# signal_distribution_board.net
KiCad netlist of a schematic drawn in EAGLE
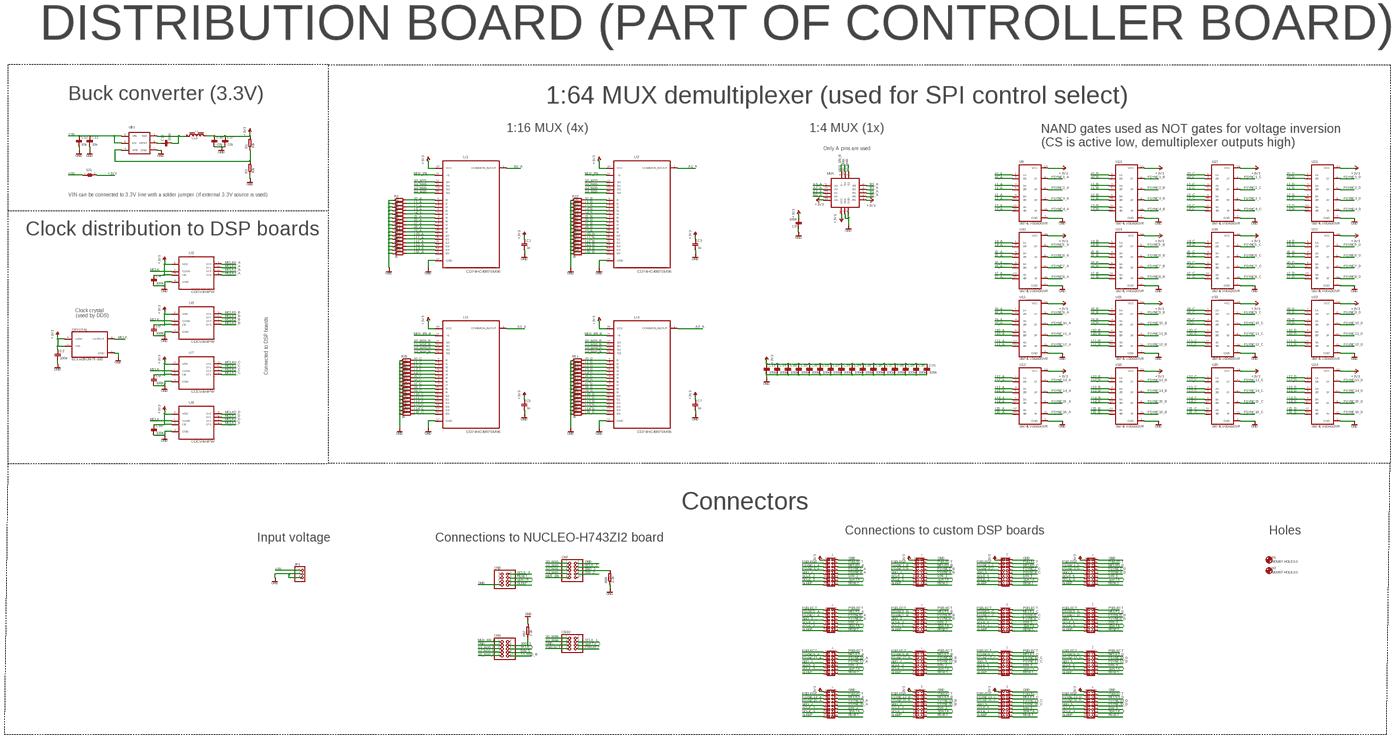
[diagram p0: schematic, sheet 1, overview]
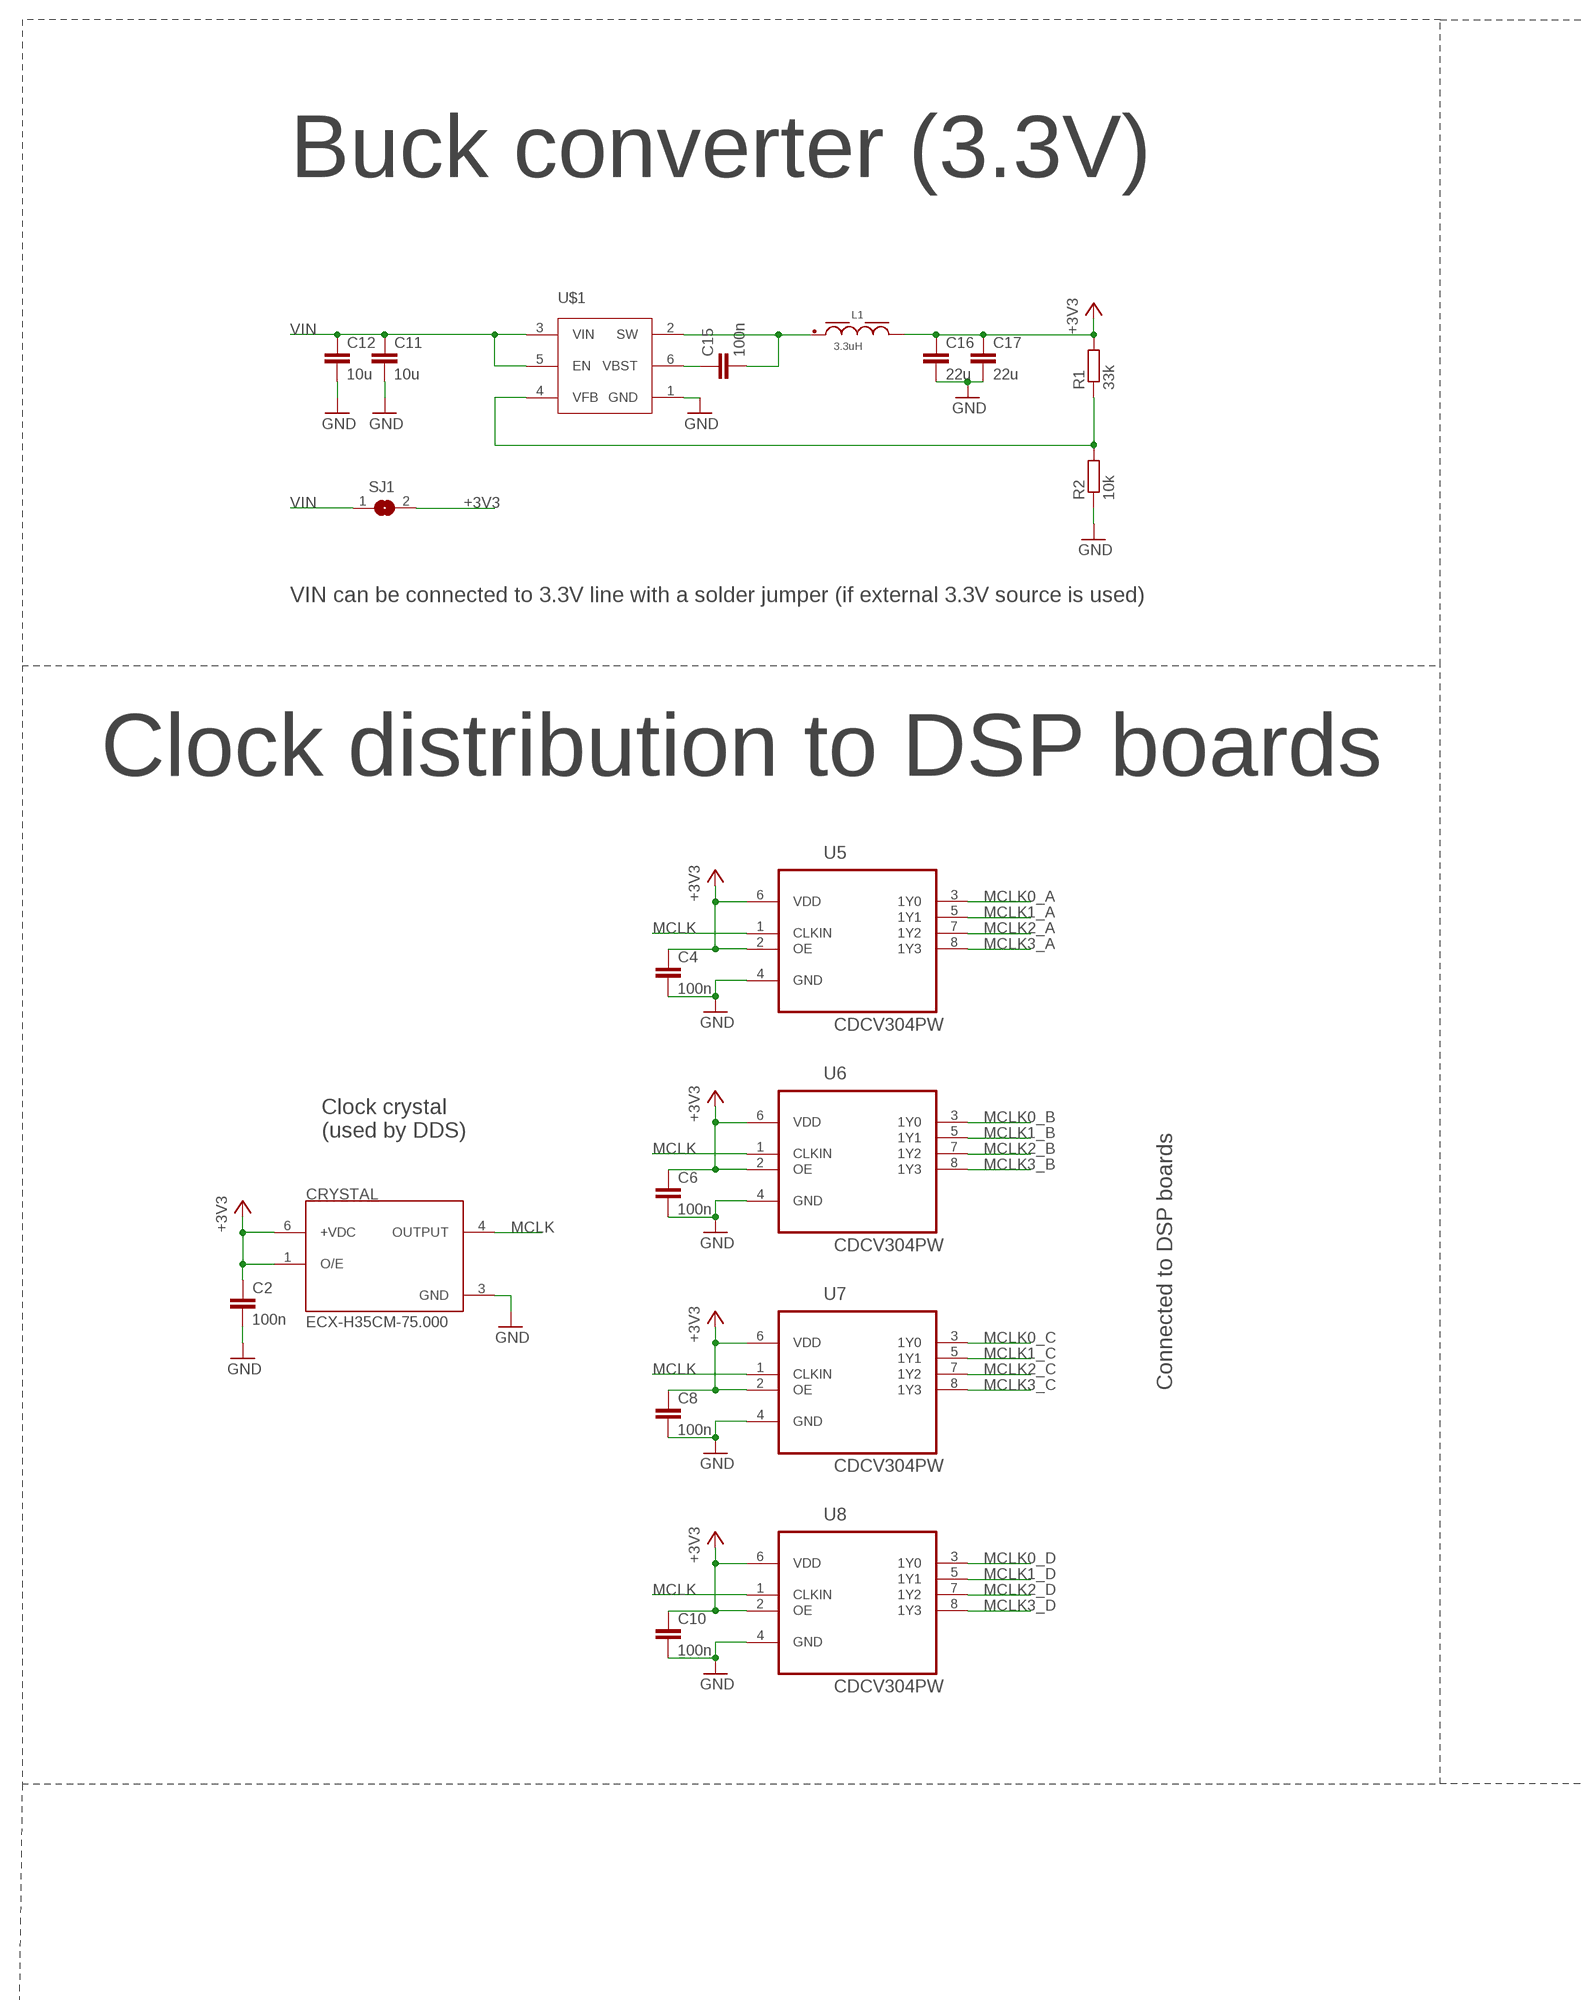
[diagram p1: schematic, sheet 1, part 1 of 8]
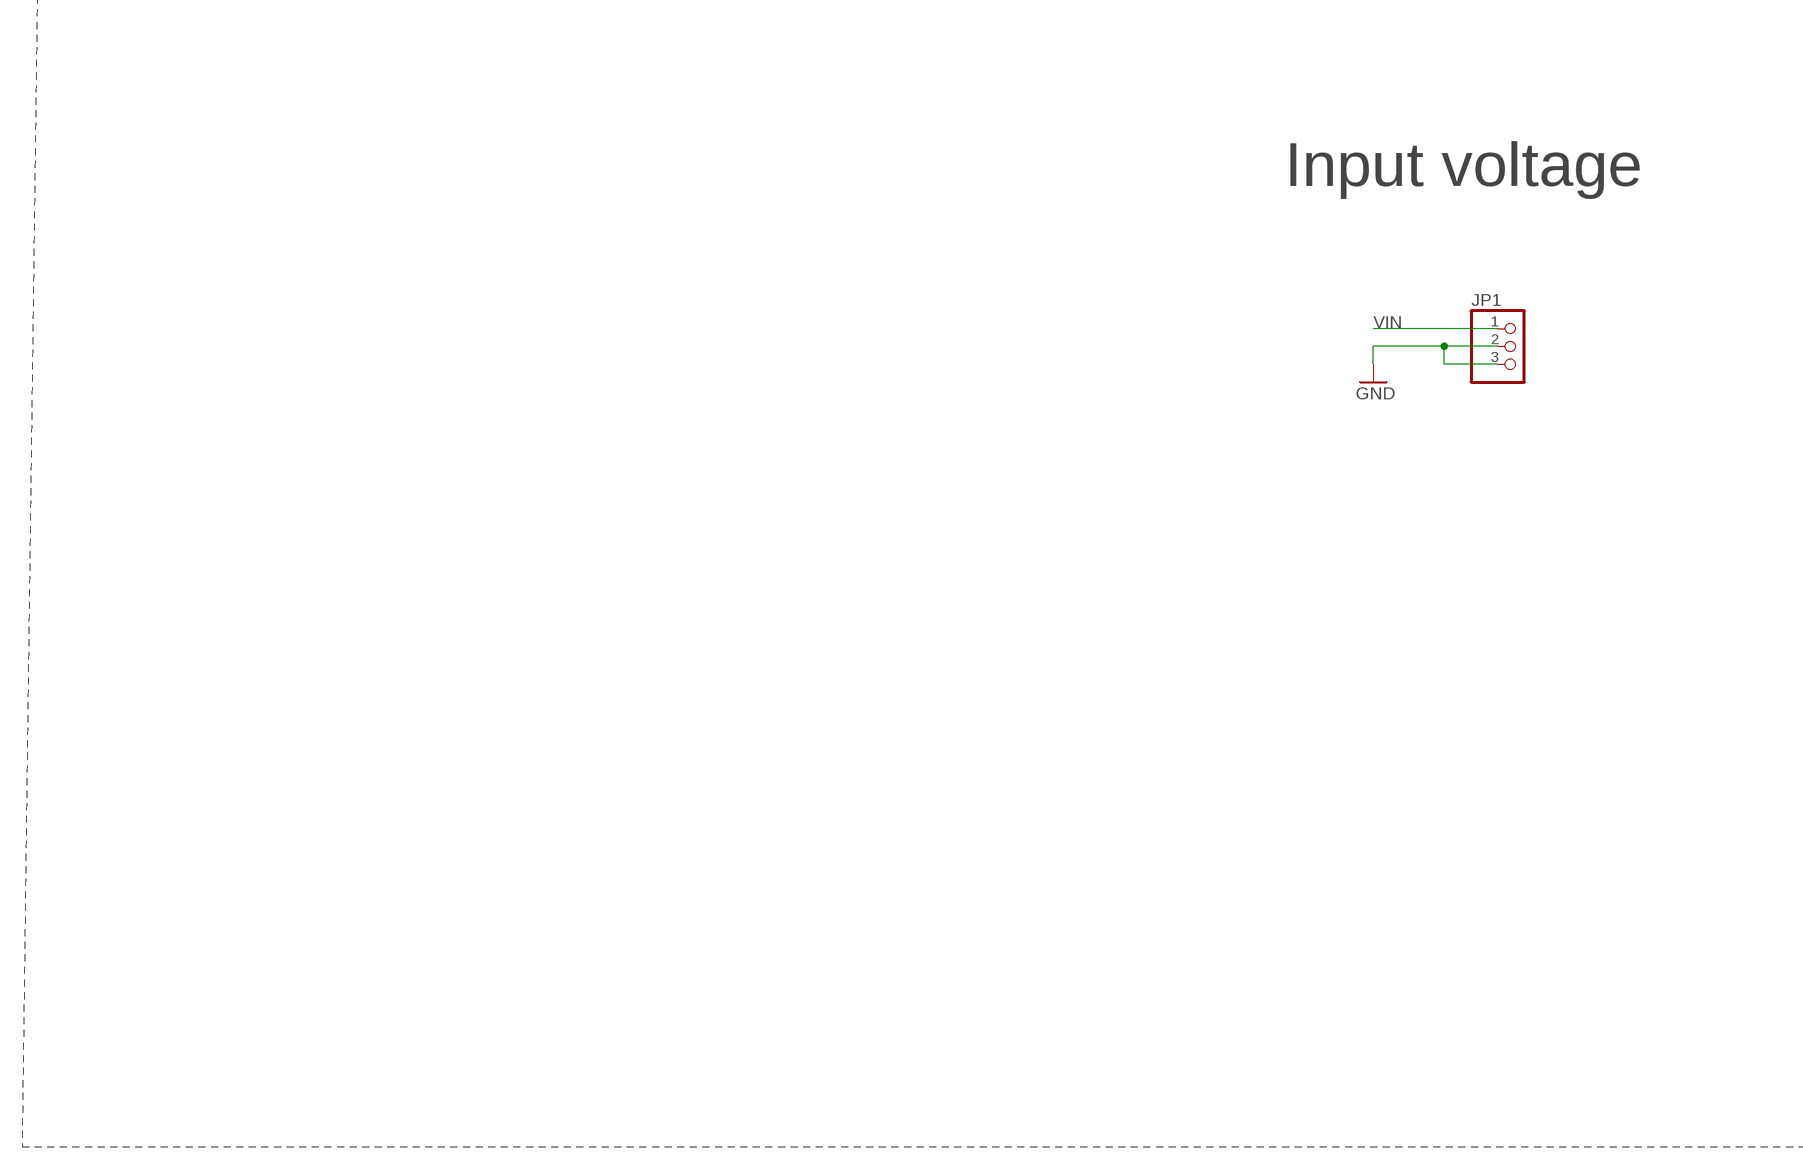
[diagram p2: schematic, sheet 1, part 2 of 8]
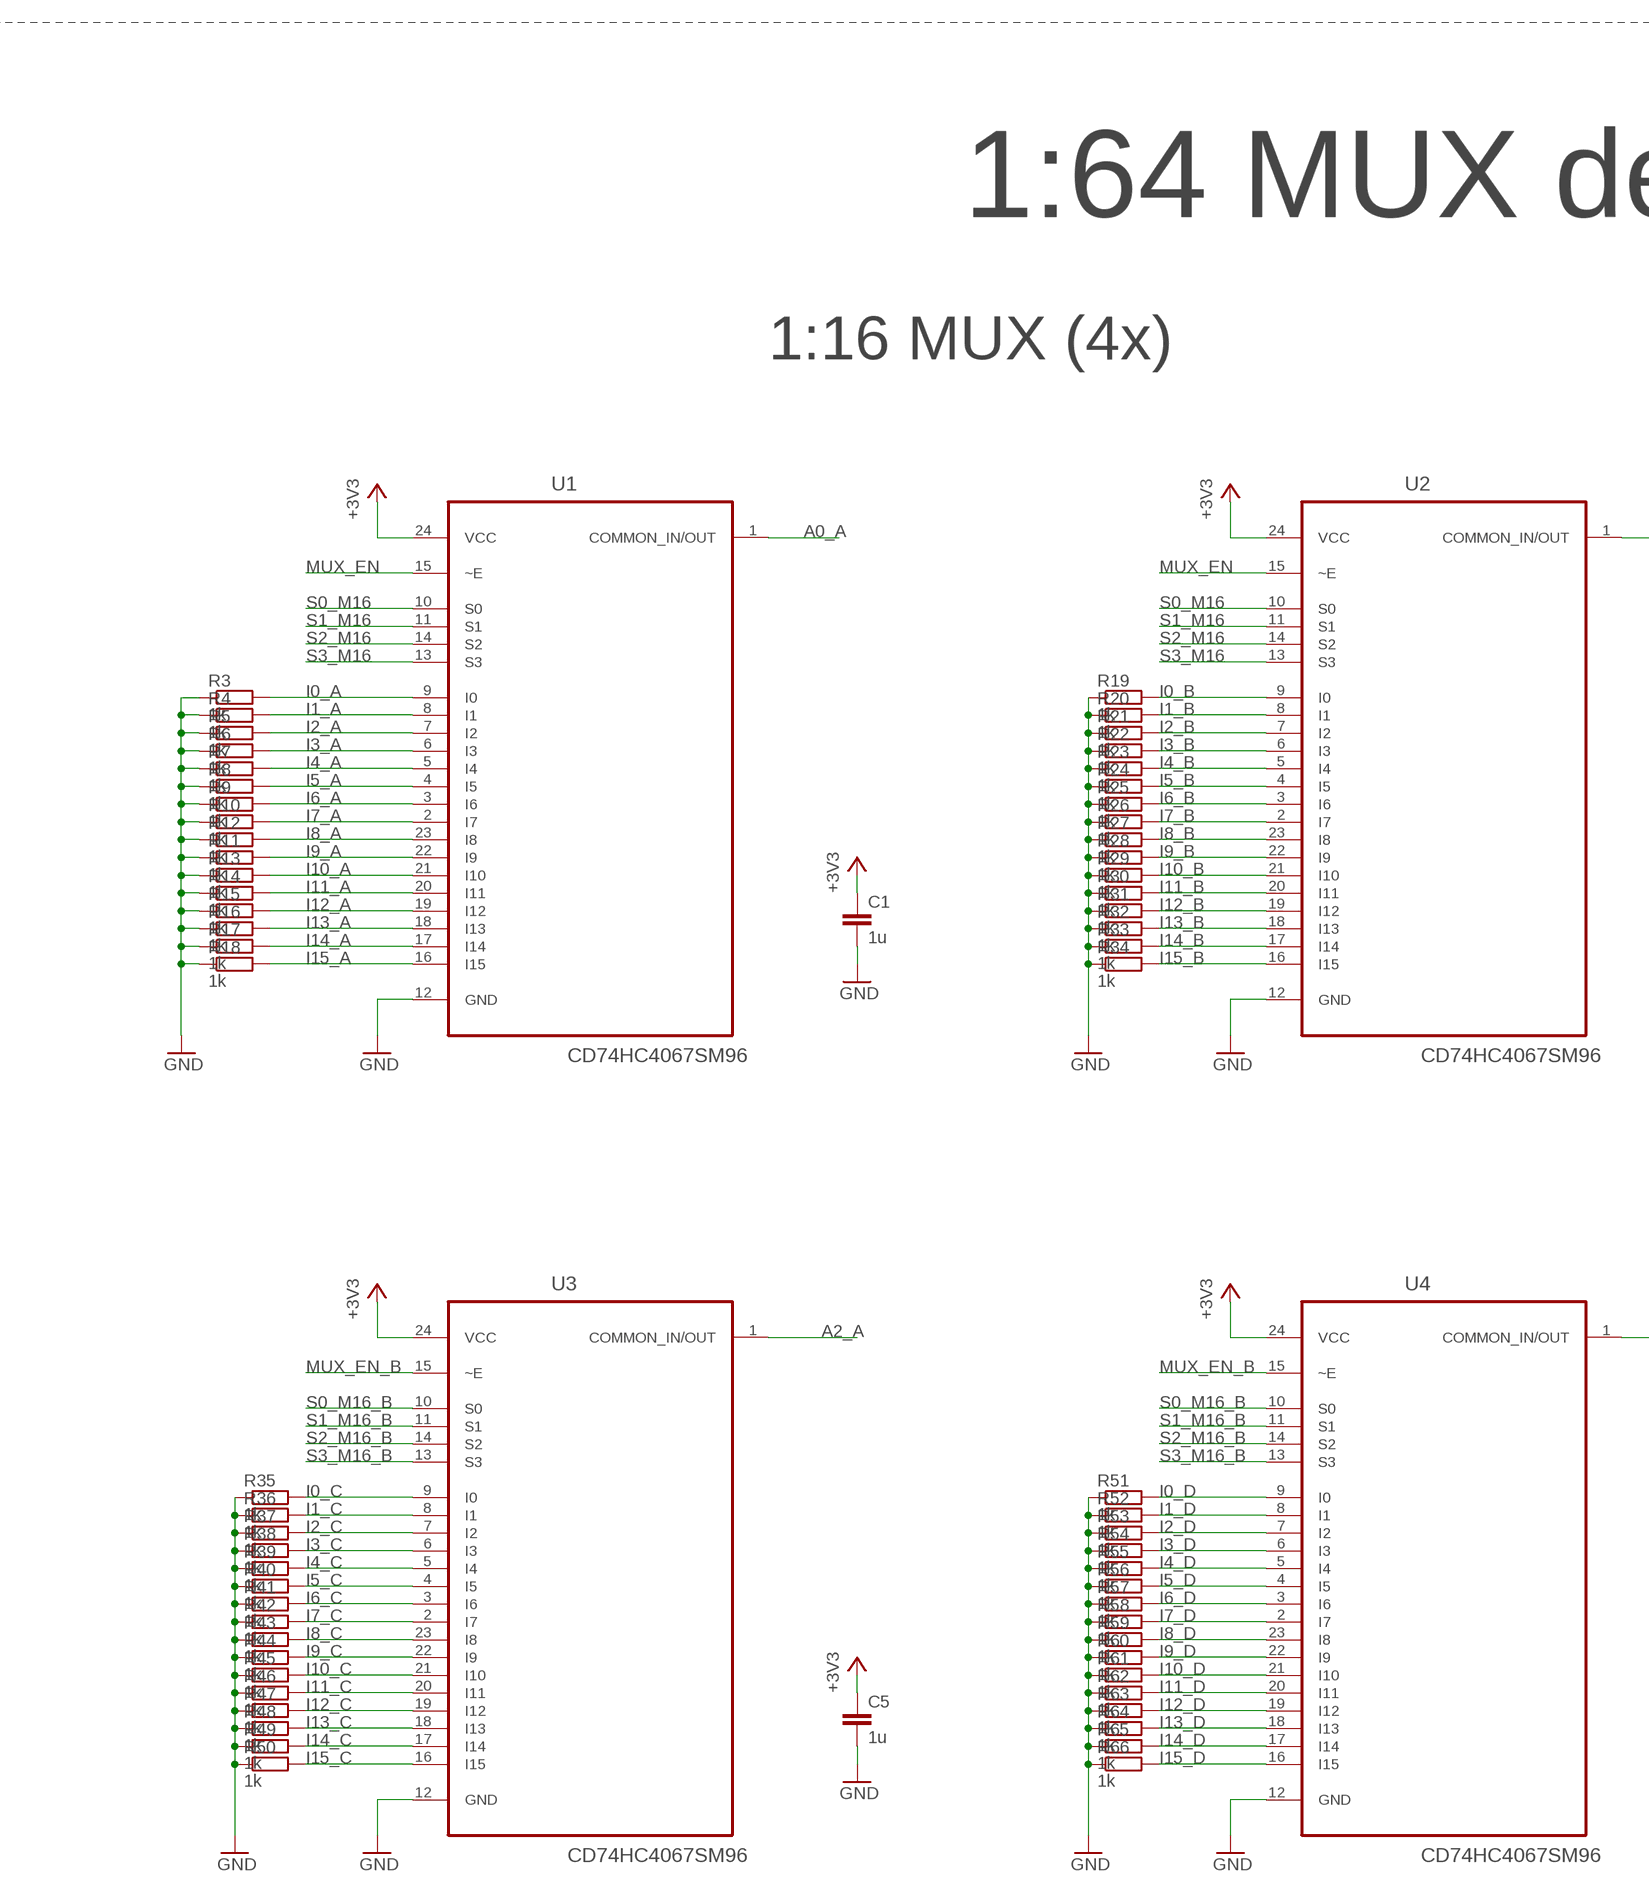
[diagram p3: schematic, sheet 1, part 3 of 8]
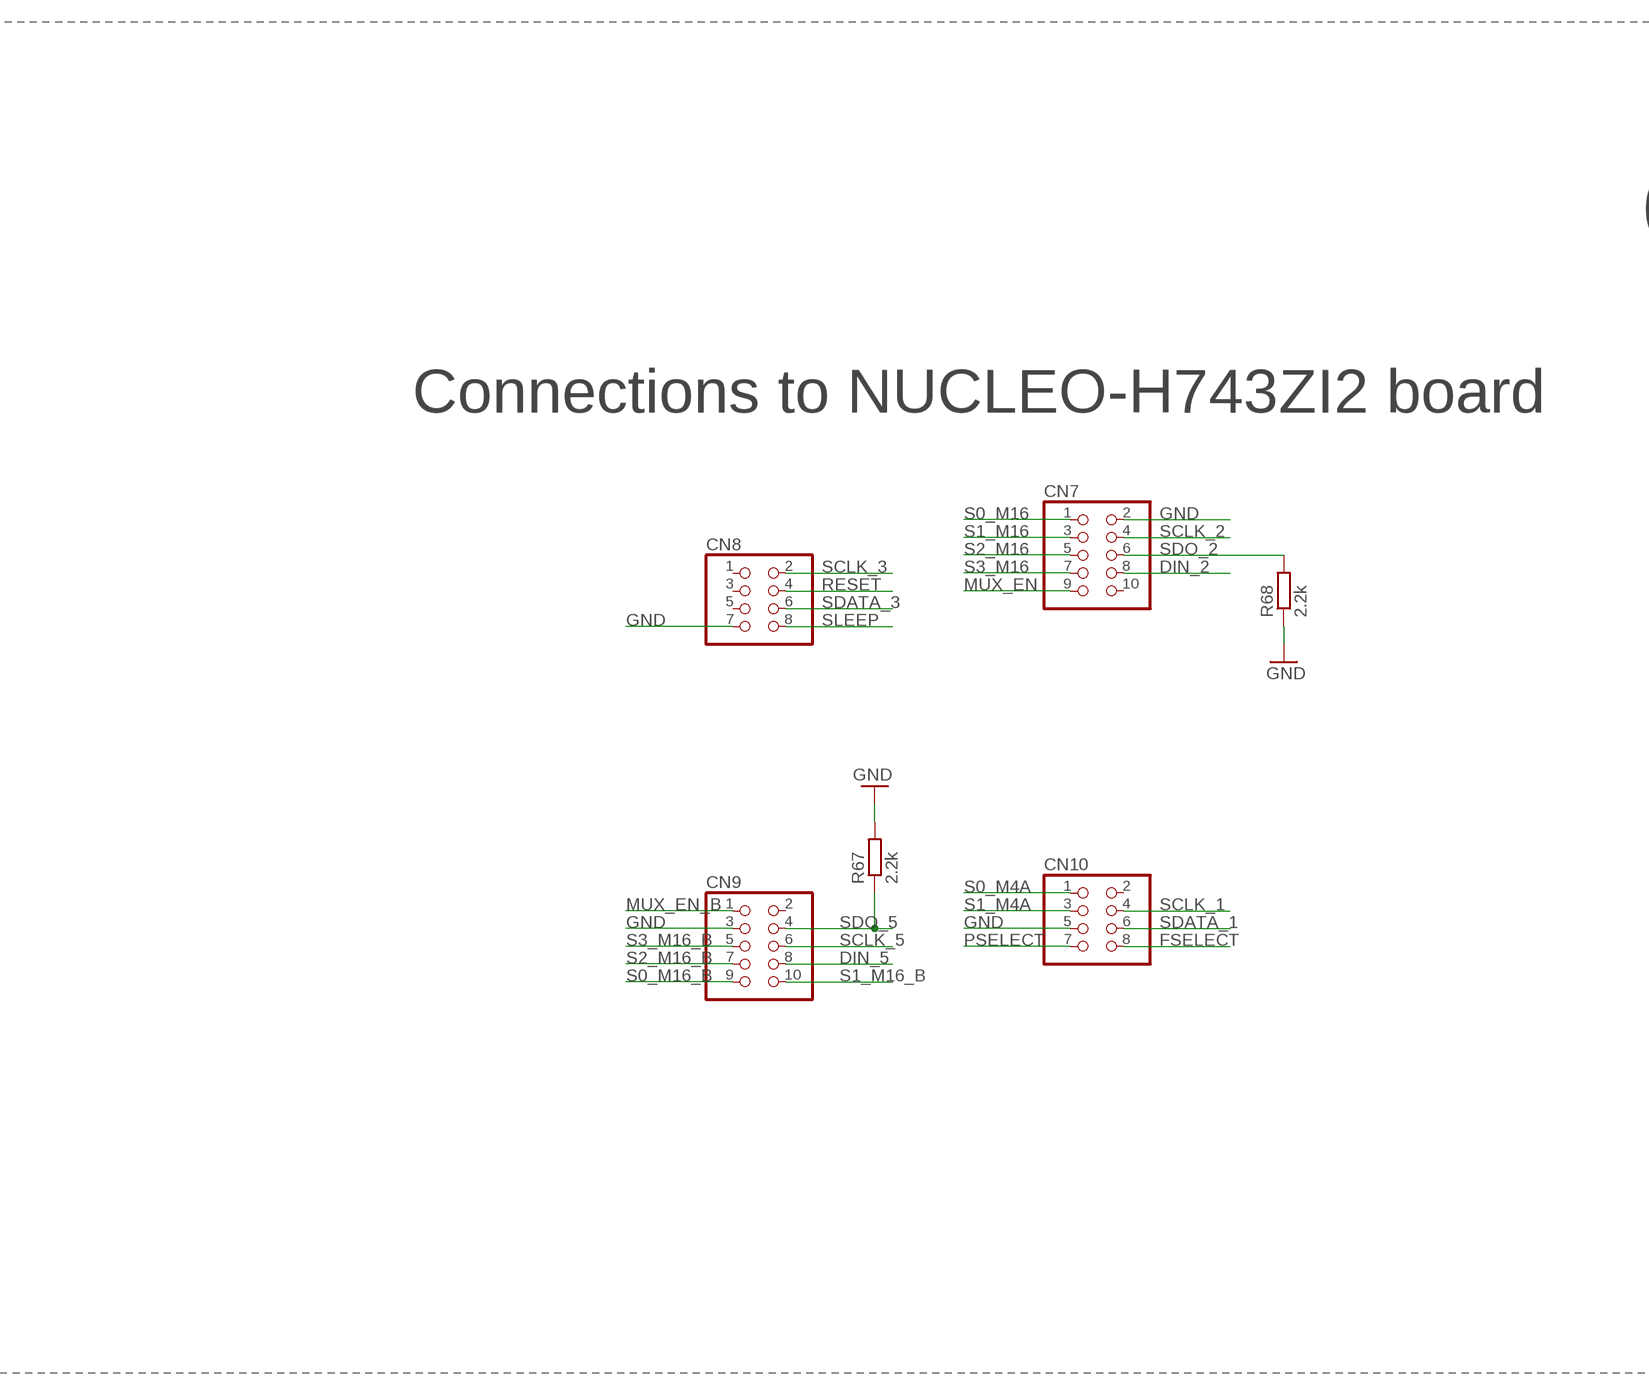
[diagram p4: schematic, sheet 1, part 4 of 8]
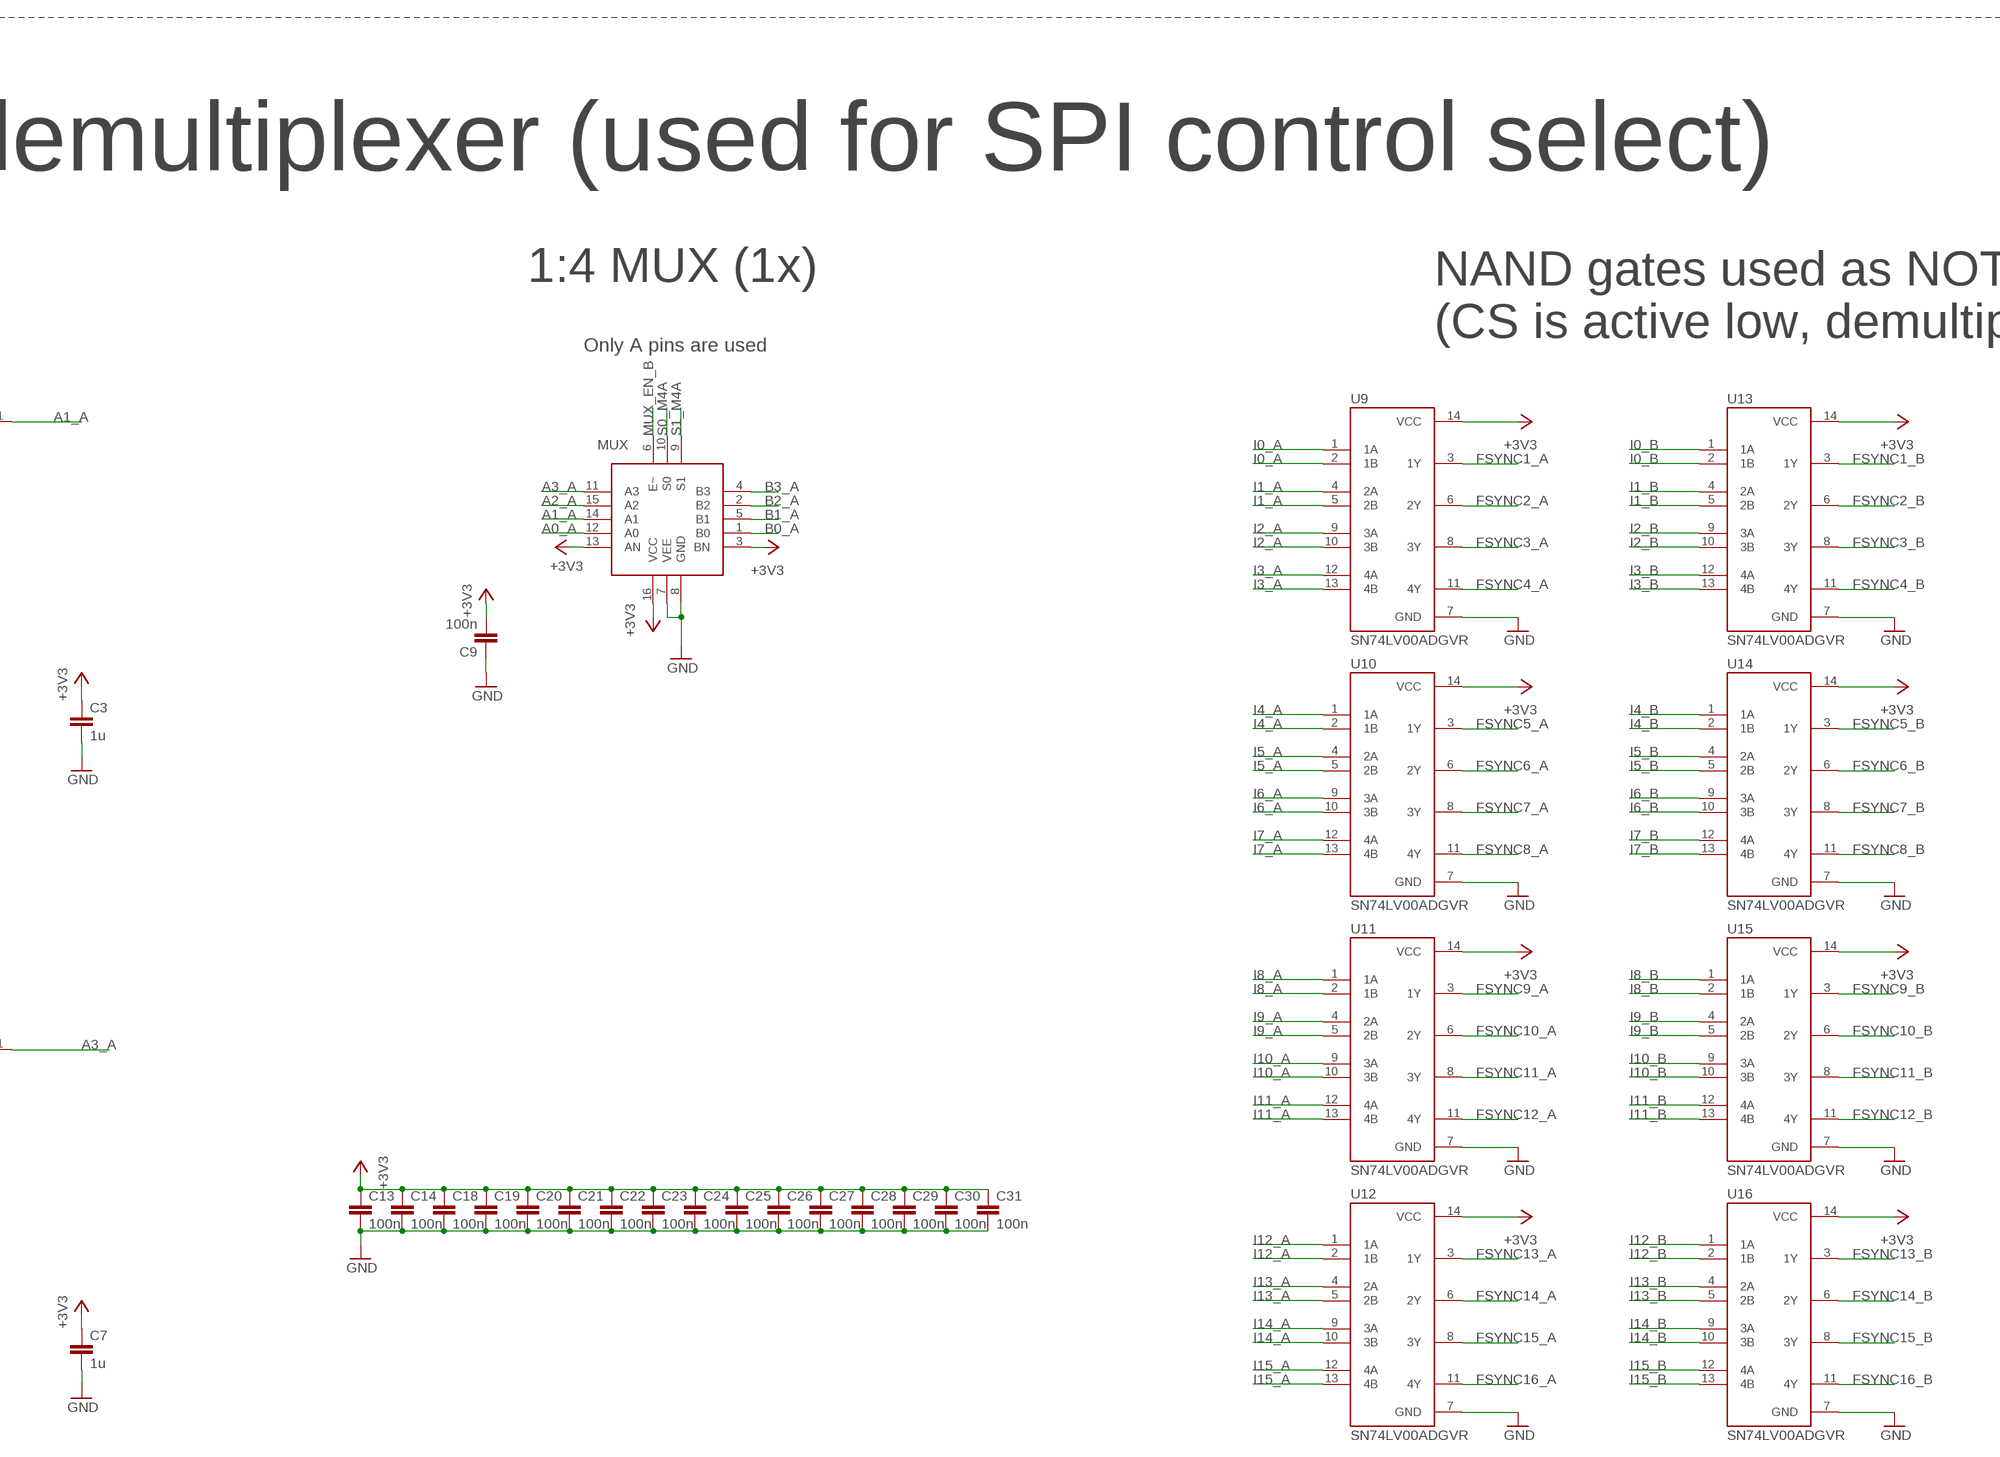
[diagram p5: schematic, sheet 1, part 5 of 8]
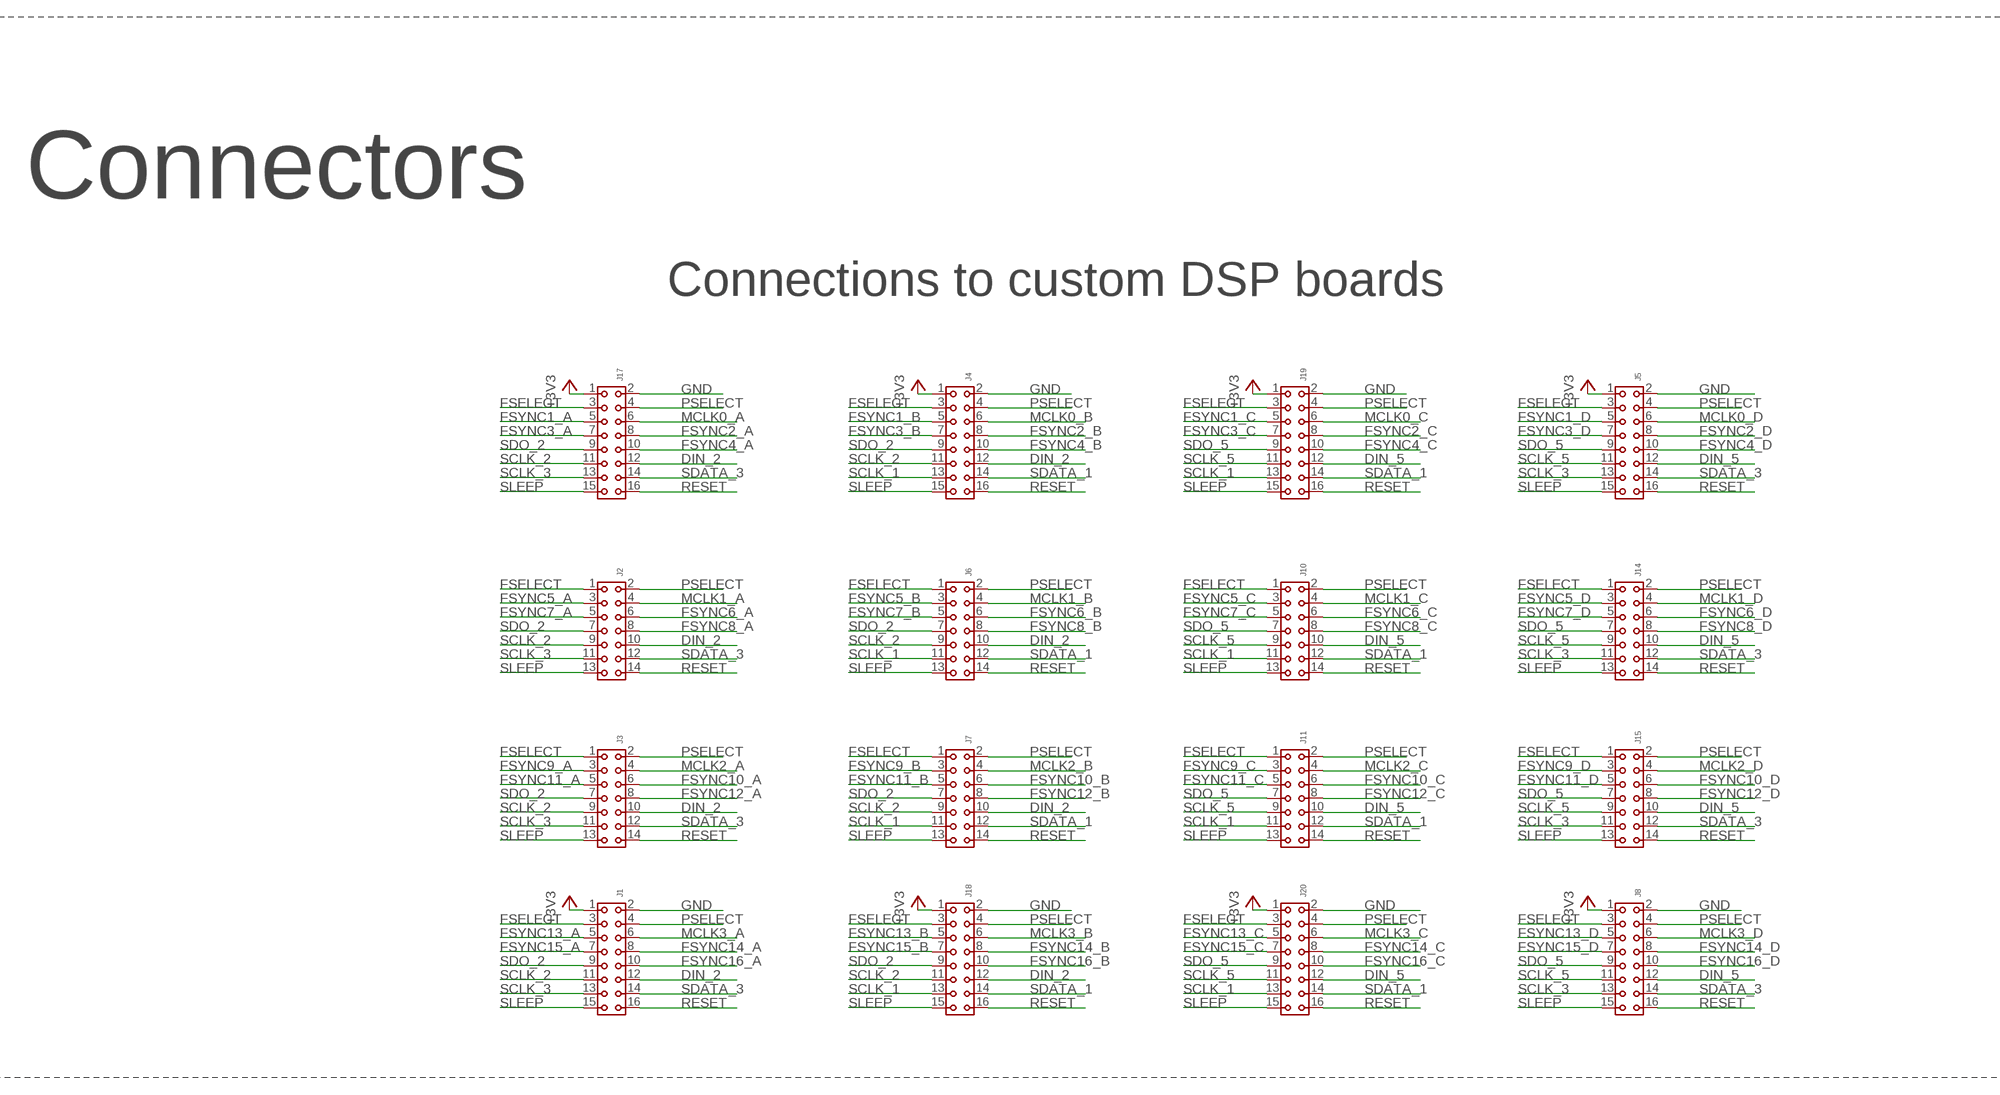
[diagram p6: schematic, sheet 1, part 6 of 8]
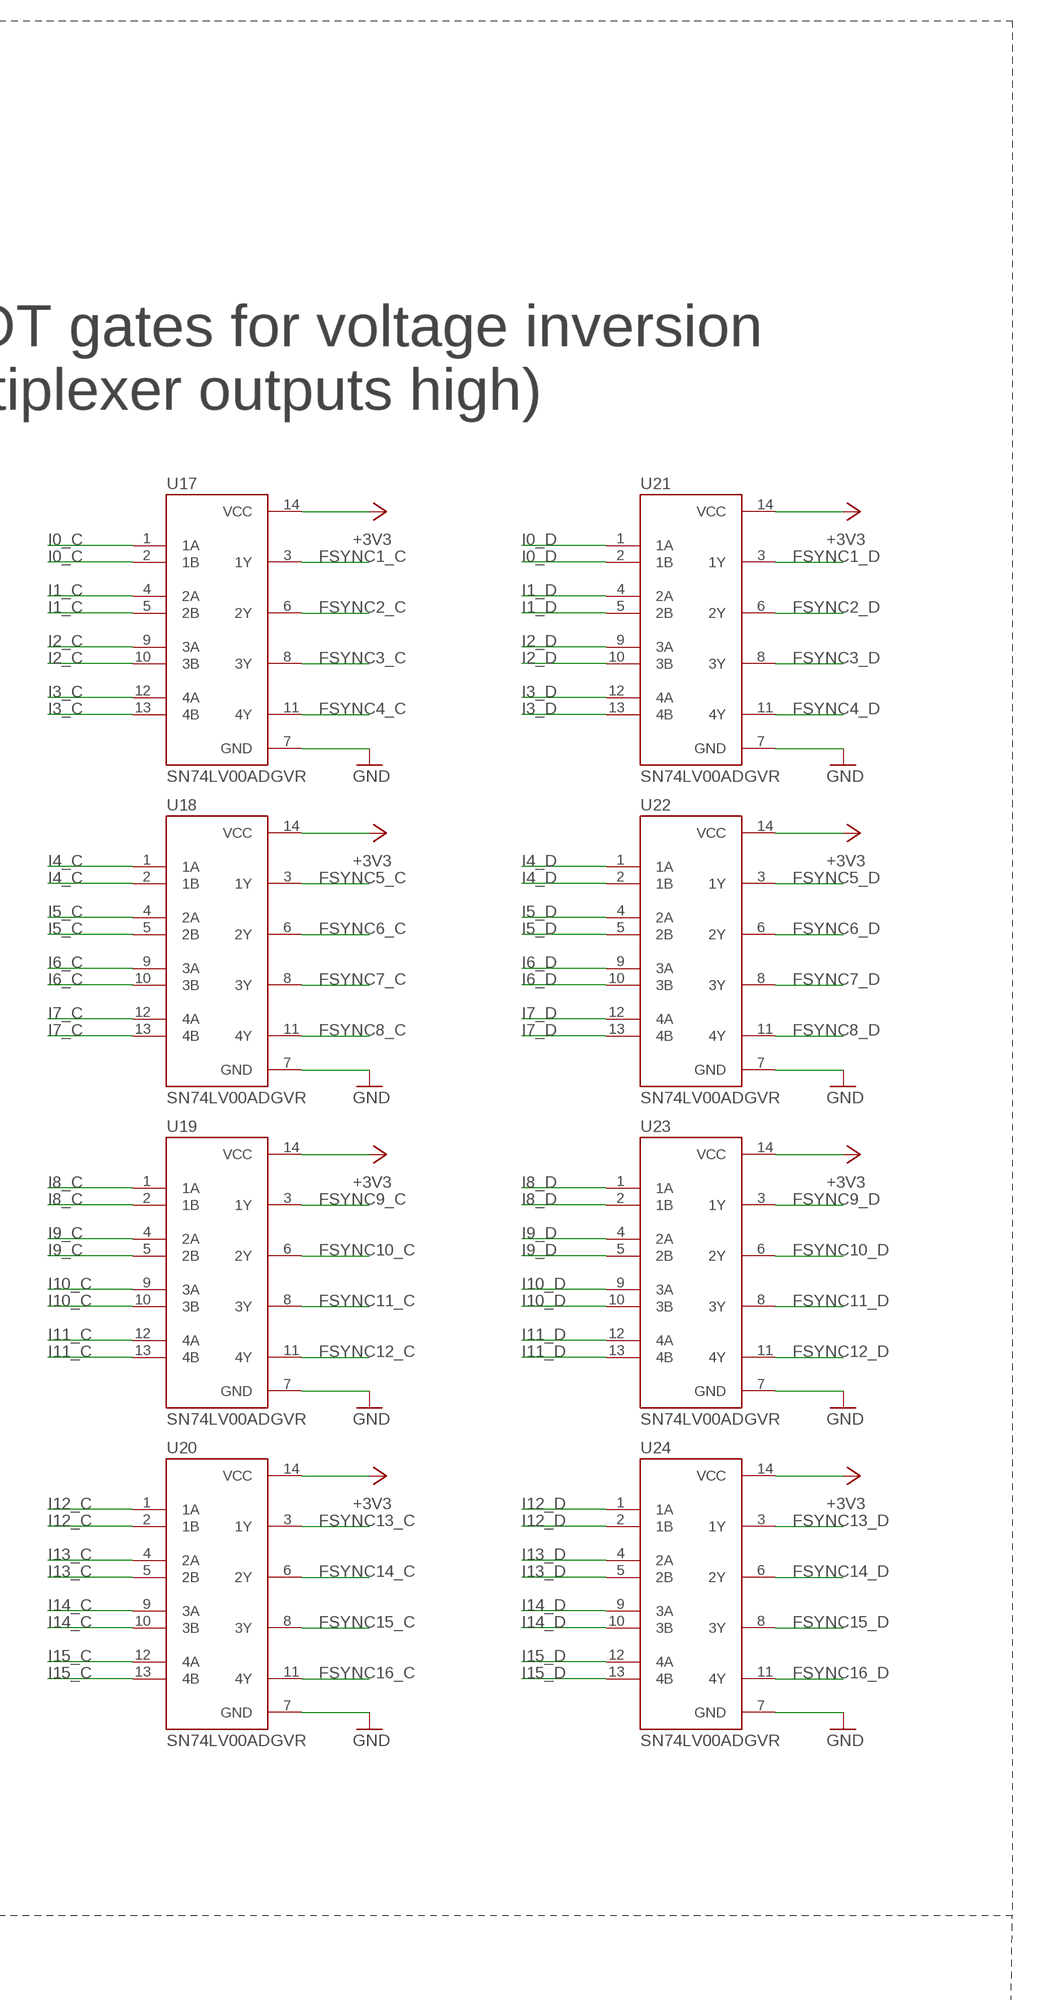
[diagram p7: schematic, sheet 1, part 7 of 8]
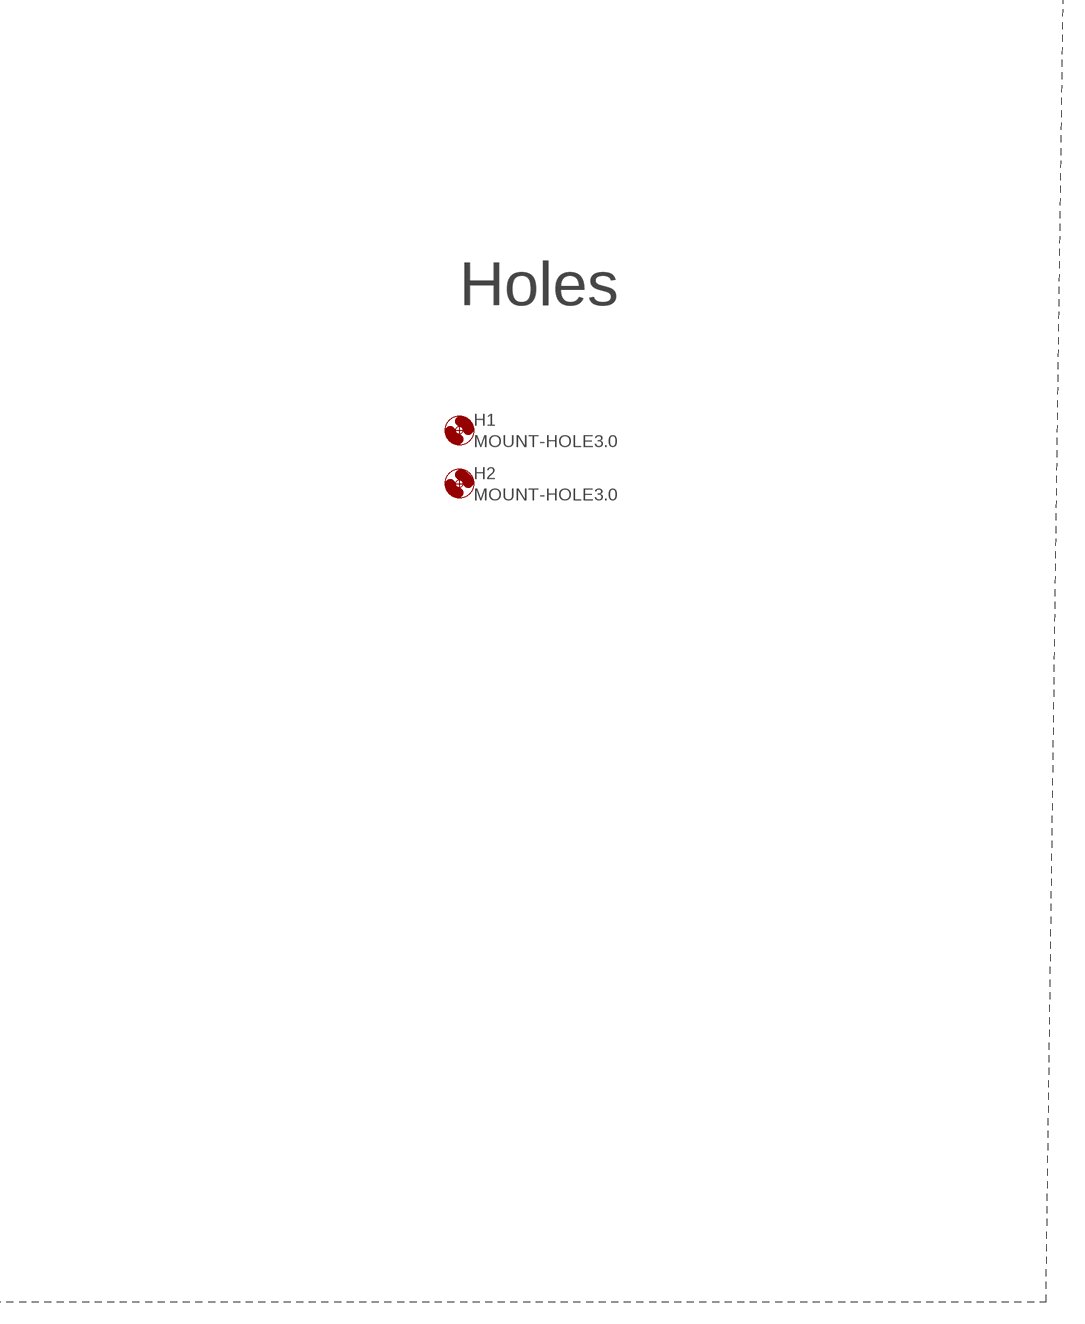
[diagram p8: schematic, sheet 1, part 8 of 8]

(export (version "E")
  (design (tool "Eeschema 10.0.6"))
  (components
    (comp (ref "C1")
      (value "1u")
      (footprint "eagle-import:C0603")
      (libsource (lib "eagle-import") (part "C-EUC0603"))
    )
    (comp (ref "C2")
      (value "100n")
      (footprint "eagle-import:C0603")
      (libsource (lib "eagle-import") (part "C-EUC0603"))
    )
    (comp (ref "C3")
      (value "1u")
      (footprint "eagle-import:C0603")
      (libsource (lib "eagle-import") (part "C-EUC0603"))
    )
    (comp (ref "C4")
      (value "100n")
      (footprint "eagle-import:C0603")
      (libsource (lib "eagle-import") (part "C-EUC0603"))
    )
    (comp (ref "C5")
      (value "1u")
      (footprint "eagle-import:C0603")
      (libsource (lib "eagle-import") (part "C-EUC0603"))
    )
    (comp (ref "C6")
      (value "100n")
      (footprint "eagle-import:C0603")
      (libsource (lib "eagle-import") (part "C-EUC0603"))
    )
    (comp (ref "C7")
      (value "1u")
      (footprint "eagle-import:C0603")
      (libsource (lib "eagle-import") (part "C-EUC0603"))
    )
    (comp (ref "C8")
      (value "100n")
      (footprint "eagle-import:C0603")
      (libsource (lib "eagle-import") (part "C-EUC0603"))
    )
    (comp (ref "C9")
      (value "100n")
      (footprint "eagle-import:C0603")
      (libsource (lib "eagle-import") (part "C-EUC0603"))
    )
    (comp (ref "C10")
      (value "100n")
      (footprint "eagle-import:C0603")
      (libsource (lib "eagle-import") (part "C-EUC0603"))
    )
    (comp (ref "C11")
      (value "10u")
      (footprint "eagle-import:C0805")
      (libsource (lib "eagle-import") (part "C-EUC0805"))
    )
    (comp (ref "C12")
      (value "10u")
      (footprint "eagle-import:C0805")
      (libsource (lib "eagle-import") (part "C-EUC0805"))
    )
    (comp (ref "C13")
      (value "100n")
      (footprint "eagle-import:C0603")
      (libsource (lib "eagle-import") (part "C-EUC0603"))
    )
    (comp (ref "C14")
      (value "100n")
      (footprint "eagle-import:C0603")
      (libsource (lib "eagle-import") (part "C-EUC0603"))
    )
    (comp (ref "C15")
      (value "100n")
      (footprint "eagle-import:C0603")
      (libsource (lib "eagle-import") (part "C-EUC0603"))
    )
    (comp (ref "C16")
      (value "22u")
      (footprint "eagle-import:C1206")
      (libsource (lib "eagle-import") (part "C-EUC1206"))
    )
    (comp (ref "C17")
      (value "22u")
      (footprint "eagle-import:C1206")
      (libsource (lib "eagle-import") (part "C-EUC1206"))
    )
    (comp (ref "C18")
      (value "100n")
      (footprint "eagle-import:C0603")
      (libsource (lib "eagle-import") (part "C-EUC0603"))
    )
    (comp (ref "C19")
      (value "100n")
      (footprint "eagle-import:C0603")
      (libsource (lib "eagle-import") (part "C-EUC0603"))
    )
    (comp (ref "C20")
      (value "100n")
      (footprint "eagle-import:C0603")
      (libsource (lib "eagle-import") (part "C-EUC0603"))
    )
    (comp (ref "C21")
      (value "100n")
      (footprint "eagle-import:C0603")
      (libsource (lib "eagle-import") (part "C-EUC0603"))
    )
    (comp (ref "C22")
      (value "100n")
      (footprint "eagle-import:C0603")
      (libsource (lib "eagle-import") (part "C-EUC0603"))
    )
    (comp (ref "C23")
      (value "100n")
      (footprint "eagle-import:C0603")
      (libsource (lib "eagle-import") (part "C-EUC0603"))
    )
    (comp (ref "C24")
      (value "100n")
      (footprint "eagle-import:C0603")
      (libsource (lib "eagle-import") (part "C-EUC0603"))
    )
    (comp (ref "C25")
      (value "100n")
      (footprint "eagle-import:C0603")
      (libsource (lib "eagle-import") (part "C-EUC0603"))
    )
    (comp (ref "C26")
      (value "100n")
      (footprint "eagle-import:C0603")
      (libsource (lib "eagle-import") (part "C-EUC0603"))
    )
    (comp (ref "C27")
      (value "100n")
      (footprint "eagle-import:C0603")
      (libsource (lib "eagle-import") (part "C-EUC0603"))
    )
    (comp (ref "C28")
      (value "100n")
      (footprint "eagle-import:C0603")
      (libsource (lib "eagle-import") (part "C-EUC0603"))
    )
    (comp (ref "C29")
      (value "100n")
      (footprint "eagle-import:C0603")
      (libsource (lib "eagle-import") (part "C-EUC0603"))
    )
    (comp (ref "C30")
      (value "100n")
      (footprint "eagle-import:C0603")
      (libsource (lib "eagle-import") (part "C-EUC0603"))
    )
    (comp (ref "C31")
      (value "100n")
      (footprint "eagle-import:C0603")
      (libsource (lib "eagle-import") (part "C-EUC0603"))
    )
    (comp (ref "CN7")
      (value "PINHD-2X5")
      (footprint "eagle-import:2X05")
      (libsource (lib "eagle-import") (part "PINHD-2X5"))
    )
    (comp (ref "CN8")
      (value "PINHD-2X4")
      (footprint "eagle-import:2X04")
      (libsource (lib "eagle-import") (part "PINHD-2X4"))
    )
    (comp (ref "CN9")
      (value "PINHD-2X5")
      (footprint "eagle-import:2X05")
      (libsource (lib "eagle-import") (part "PINHD-2X5"))
    )
    (comp (ref "CN10")
      (value "PINHD-2X4")
      (footprint "eagle-import:2X04")
      (libsource (lib "eagle-import") (part "PINHD-2X4"))
    )
    (comp (ref "CRYSTAL")
      (value "ECX-H35CM-75.000")
      (footprint "eagle-import:OSC_ECX-H35CM-75.000")
      (fields (field (name "MF") "ECS International"))
      (libsource (lib "eagle-import") (part "ECX-H35CM-75.000"))
    )
    (comp (ref "H1")
      (value "MOUNT-HOLE3.0")
      (footprint "eagle-import:3,0")
      (libsource (lib "eagle-import") (part "MOUNT-HOLE3.0"))
    )
    (comp (ref "H2")
      (value "MOUNT-HOLE3.0")
      (footprint "eagle-import:3,0")
      (libsource (lib "eagle-import") (part "MOUNT-HOLE3.0"))
    )
    (comp (ref "J1")
      (value "6130XX243121_613016243121")
      (footprint "eagle-import:613016243121")
      (libsource (lib "eagle-import") (part "6130XX243121_613016243121"))
    )
    (comp (ref "J2")
      (value "6130XX243121_613014243121")
      (footprint "eagle-import:613014243121")
      (libsource (lib "eagle-import") (part "6130XX243121_613014243121"))
    )
    (comp (ref "J3")
      (value "6130XX243121_613014243121")
      (footprint "eagle-import:613014243121")
      (libsource (lib "eagle-import") (part "6130XX243121_613014243121"))
    )
    (comp (ref "J4")
      (value "6130XX243121_613016243121")
      (footprint "eagle-import:613016243121")
      (libsource (lib "eagle-import") (part "6130XX243121_613016243121"))
    )
    (comp (ref "J5")
      (value "6130XX243121_613016243121")
      (footprint "eagle-import:613016243121")
      (libsource (lib "eagle-import") (part "6130XX243121_613016243121"))
    )
    (comp (ref "J6")
      (value "6130XX243121_613014243121")
      (footprint "eagle-import:613014243121")
      (libsource (lib "eagle-import") (part "6130XX243121_613014243121"))
    )
    (comp (ref "J7")
      (value "6130XX243121_613014243121")
      (footprint "eagle-import:613014243121")
      (libsource (lib "eagle-import") (part "6130XX243121_613014243121"))
    )
    (comp (ref "J8")
      (value "6130XX243121_613016243121")
      (footprint "eagle-import:613016243121")
      (libsource (lib "eagle-import") (part "6130XX243121_613016243121"))
    )
    (comp (ref "J10")
      (value "6130XX243121_613014243121")
      (footprint "eagle-import:613014243121")
      (libsource (lib "eagle-import") (part "6130XX243121_613014243121"))
    )
    (comp (ref "J11")
      (value "6130XX243121_613014243121")
      (footprint "eagle-import:613014243121")
      (libsource (lib "eagle-import") (part "6130XX243121_613014243121"))
    )
    (comp (ref "J14")
      (value "6130XX243121_613014243121")
      (footprint "eagle-import:613014243121")
      (libsource (lib "eagle-import") (part "6130XX243121_613014243121"))
    )
    (comp (ref "J15")
      (value "6130XX243121_613014243121")
      (footprint "eagle-import:613014243121")
      (libsource (lib "eagle-import") (part "6130XX243121_613014243121"))
    )
    (comp (ref "J17")
      (value "6130XX243121_613016243121")
      (footprint "eagle-import:613016243121")
      (libsource (lib "eagle-import") (part "6130XX243121_613016243121"))
    )
    (comp (ref "J18")
      (value "6130XX243121_613016243121")
      (footprint "eagle-import:613016243121")
      (libsource (lib "eagle-import") (part "6130XX243121_613016243121"))
    )
    (comp (ref "J19")
      (value "6130XX243121_613016243121")
      (footprint "eagle-import:613016243121")
      (libsource (lib "eagle-import") (part "6130XX243121_613016243121"))
    )
    (comp (ref "J20")
      (value "6130XX243121_613016243121")
      (footprint "eagle-import:613016243121")
      (libsource (lib "eagle-import") (part "6130XX243121_613016243121"))
    )
    (comp (ref "JP1")
      (value "PINHD-1X3")
      (footprint "eagle-import:1X03")
      (libsource (lib "eagle-import") (part "PINHD-1X3"))
    )
    (comp (ref "L1")
      (value "3.3uH")
      (footprint "eagle-import:WE-PD_7345P")
      (libsource (lib "eagle-import") (part "WE-PD_7345P_7447773033"))
    )
    (comp (ref "MUX")
      (value "CD74HC4052M96")
      (footprint "eagle-import:SOIC127P600X175-16N")
      (libsource (lib "eagle-import") (part "CD74HC4052M96"))
    )
    (comp (ref "R1")
      (value "33k")
      (footprint "eagle-import:R0603")
      (libsource (lib "eagle-import") (part "R-EU_R0603"))
    )
    (comp (ref "R2")
      (value "10k")
      (footprint "eagle-import:R0603")
      (libsource (lib "eagle-import") (part "R-EU_R0603"))
    )
    (comp (ref "R3")
      (value "1k")
      (footprint "eagle-import:R0603")
      (libsource (lib "eagle-import") (part "R-EU_R0603"))
    )
    (comp (ref "R4")
      (value "1k")
      (footprint "eagle-import:R0603")
      (libsource (lib "eagle-import") (part "R-EU_R0603"))
    )
    (comp (ref "R5")
      (value "1k")
      (footprint "eagle-import:R0603")
      (libsource (lib "eagle-import") (part "R-EU_R0603"))
    )
    (comp (ref "R6")
      (value "1k")
      (footprint "eagle-import:R0603")
      (libsource (lib "eagle-import") (part "R-EU_R0603"))
    )
    (comp (ref "R7")
      (value "1k")
      (footprint "eagle-import:R0603")
      (libsource (lib "eagle-import") (part "R-EU_R0603"))
    )
    (comp (ref "R8")
      (value "1k")
      (footprint "eagle-import:R0603")
      (libsource (lib "eagle-import") (part "R-EU_R0603"))
    )
    (comp (ref "R9")
      (value "1k")
      (footprint "eagle-import:R0603")
      (libsource (lib "eagle-import") (part "R-EU_R0603"))
    )
    (comp (ref "R10")
      (value "1k")
      (footprint "eagle-import:R0603")
      (libsource (lib "eagle-import") (part "R-EU_R0603"))
    )
    (comp (ref "R11")
      (value "1k")
      (footprint "eagle-import:R0603")
      (libsource (lib "eagle-import") (part "R-EU_R0603"))
    )
    (comp (ref "R12")
      (value "1k")
      (footprint "eagle-import:R0603")
      (libsource (lib "eagle-import") (part "R-EU_R0603"))
    )
    (comp (ref "R13")
      (value "1k")
      (footprint "eagle-import:R0603")
      (libsource (lib "eagle-import") (part "R-EU_R0603"))
    )
    (comp (ref "R14")
      (value "1k")
      (footprint "eagle-import:R0603")
      (libsource (lib "eagle-import") (part "R-EU_R0603"))
    )
    (comp (ref "R15")
      (value "1k")
      (footprint "eagle-import:R0603")
      (libsource (lib "eagle-import") (part "R-EU_R0603"))
    )
    (comp (ref "R16")
      (value "1k")
      (footprint "eagle-import:R0603")
      (libsource (lib "eagle-import") (part "R-EU_R0603"))
    )
    (comp (ref "R17")
      (value "1k")
      (footprint "eagle-import:R0603")
      (libsource (lib "eagle-import") (part "R-EU_R0603"))
    )
    (comp (ref "R18")
      (value "1k")
      (footprint "eagle-import:R0603")
      (libsource (lib "eagle-import") (part "R-EU_R0603"))
    )
    (comp (ref "R19")
      (value "1k")
      (footprint "eagle-import:R0603")
      (libsource (lib "eagle-import") (part "R-EU_R0603"))
    )
    (comp (ref "R20")
      (value "1k")
      (footprint "eagle-import:R0603")
      (libsource (lib "eagle-import") (part "R-EU_R0603"))
    )
    (comp (ref "R21")
      (value "1k")
      (footprint "eagle-import:R0603")
      (libsource (lib "eagle-import") (part "R-EU_R0603"))
    )
    (comp (ref "R22")
      (value "1k")
      (footprint "eagle-import:R0603")
      (libsource (lib "eagle-import") (part "R-EU_R0603"))
    )
    (comp (ref "R23")
      (value "1k")
      (footprint "eagle-import:R0603")
      (libsource (lib "eagle-import") (part "R-EU_R0603"))
    )
    (comp (ref "R24")
      (value "1k")
      (footprint "eagle-import:R0603")
      (libsource (lib "eagle-import") (part "R-EU_R0603"))
    )
    (comp (ref "R25")
      (value "1k")
      (footprint "eagle-import:R0603")
      (libsource (lib "eagle-import") (part "R-EU_R0603"))
    )
    (comp (ref "R26")
      (value "1k")
      (footprint "eagle-import:R0603")
      (libsource (lib "eagle-import") (part "R-EU_R0603"))
    )
    (comp (ref "R27")
      (value "1k")
      (footprint "eagle-import:R0603")
      (libsource (lib "eagle-import") (part "R-EU_R0603"))
    )
    (comp (ref "R28")
      (value "1k")
      (footprint "eagle-import:R0603")
      (libsource (lib "eagle-import") (part "R-EU_R0603"))
    )
    (comp (ref "R29")
      (value "1k")
      (footprint "eagle-import:R0603")
      (libsource (lib "eagle-import") (part "R-EU_R0603"))
    )
    (comp (ref "R30")
      (value "1k")
      (footprint "eagle-import:R0603")
      (libsource (lib "eagle-import") (part "R-EU_R0603"))
    )
    (comp (ref "R31")
      (value "1k")
      (footprint "eagle-import:R0603")
      (libsource (lib "eagle-import") (part "R-EU_R0603"))
    )
    (comp (ref "R32")
      (value "1k")
      (footprint "eagle-import:R0603")
      (libsource (lib "eagle-import") (part "R-EU_R0603"))
    )
    (comp (ref "R33")
      (value "1k")
      (footprint "eagle-import:R0603")
      (libsource (lib "eagle-import") (part "R-EU_R0603"))
    )
    (comp (ref "R34")
      (value "1k")
      (footprint "eagle-import:R0603")
      (libsource (lib "eagle-import") (part "R-EU_R0603"))
    )
    (comp (ref "R35")
      (value "1k")
      (footprint "eagle-import:R0603")
      (libsource (lib "eagle-import") (part "R-EU_R0603"))
    )
    (comp (ref "R36")
      (value "1k")
      (footprint "eagle-import:R0603")
      (libsource (lib "eagle-import") (part "R-EU_R0603"))
    )
    (comp (ref "R37")
      (value "1k")
      (footprint "eagle-import:R0603")
      (libsource (lib "eagle-import") (part "R-EU_R0603"))
    )
    (comp (ref "R38")
      (value "1k")
      (footprint "eagle-import:R0603")
      (libsource (lib "eagle-import") (part "R-EU_R0603"))
    )
    (comp (ref "R39")
      (value "1k")
      (footprint "eagle-import:R0603")
      (libsource (lib "eagle-import") (part "R-EU_R0603"))
    )
    (comp (ref "R40")
      (value "1k")
      (footprint "eagle-import:R0603")
      (libsource (lib "eagle-import") (part "R-EU_R0603"))
    )
    (comp (ref "R41")
      (value "1k")
      (footprint "eagle-import:R0603")
      (libsource (lib "eagle-import") (part "R-EU_R0603"))
    )
    (comp (ref "R42")
      (value "1k")
      (footprint "eagle-import:R0603")
      (libsource (lib "eagle-import") (part "R-EU_R0603"))
    )
    (comp (ref "R43")
      (value "1k")
      (footprint "eagle-import:R0603")
      (libsource (lib "eagle-import") (part "R-EU_R0603"))
    )
    (comp (ref "R44")
      (value "1k")
      (footprint "eagle-import:R0603")
      (libsource (lib "eagle-import") (part "R-EU_R0603"))
    )
    (comp (ref "R45")
      (value "1k")
      (footprint "eagle-import:R0603")
      (libsource (lib "eagle-import") (part "R-EU_R0603"))
    )
    (comp (ref "R46")
      (value "1k")
      (footprint "eagle-import:R0603")
      (libsource (lib "eagle-import") (part "R-EU_R0603"))
    )
    (comp (ref "R47")
      (value "1k")
      (footprint "eagle-import:R0603")
      (libsource (lib "eagle-import") (part "R-EU_R0603"))
    )
    (comp (ref "R48")
      (value "1k")
      (footprint "eagle-import:R0603")
      (libsource (lib "eagle-import") (part "R-EU_R0603"))
    )
    (comp (ref "R49")
      (value "1k")
      (footprint "eagle-import:R0603")
      (libsource (lib "eagle-import") (part "R-EU_R0603"))
    )
    (comp (ref "R50")
      (value "1k")
      (footprint "eagle-import:R0603")
      (libsource (lib "eagle-import") (part "R-EU_R0603"))
    )
    (comp (ref "R51")
      (value "1k")
      (footprint "eagle-import:R0603")
      (libsource (lib "eagle-import") (part "R-EU_R0603"))
    )
    (comp (ref "R52")
      (value "1k")
      (footprint "eagle-import:R0603")
      (libsource (lib "eagle-import") (part "R-EU_R0603"))
    )
    (comp (ref "R53")
      (value "1k")
      (footprint "eagle-import:R0603")
      (libsource (lib "eagle-import") (part "R-EU_R0603"))
    )
    (comp (ref "R54")
      (value "1k")
      (footprint "eagle-import:R0603")
      (libsource (lib "eagle-import") (part "R-EU_R0603"))
    )
    (comp (ref "R55")
      (value "1k")
      (footprint "eagle-import:R0603")
      (libsource (lib "eagle-import") (part "R-EU_R0603"))
    )
    (comp (ref "R56")
      (value "1k")
      (footprint "eagle-import:R0603")
      (libsource (lib "eagle-import") (part "R-EU_R0603"))
    )
    (comp (ref "R57")
      (value "1k")
      (footprint "eagle-import:R0603")
      (libsource (lib "eagle-import") (part "R-EU_R0603"))
    )
    (comp (ref "R58")
      (value "1k")
      (footprint "eagle-import:R0603")
      (libsource (lib "eagle-import") (part "R-EU_R0603"))
    )
    (comp (ref "R59")
      (value "1k")
      (footprint "eagle-import:R0603")
      (libsource (lib "eagle-import") (part "R-EU_R0603"))
    )
    (comp (ref "R60")
      (value "1k")
      (footprint "eagle-import:R0603")
      (libsource (lib "eagle-import") (part "R-EU_R0603"))
    )
    (comp (ref "R61")
      (value "1k")
      (footprint "eagle-import:R0603")
      (libsource (lib "eagle-import") (part "R-EU_R0603"))
    )
    (comp (ref "R62")
      (value "1k")
      (footprint "eagle-import:R0603")
      (libsource (lib "eagle-import") (part "R-EU_R0603"))
    )
    (comp (ref "R63")
      (value "1k")
      (footprint "eagle-import:R0603")
      (libsource (lib "eagle-import") (part "R-EU_R0603"))
    )
    (comp (ref "R64")
      (value "1k")
      (footprint "eagle-import:R0603")
      (libsource (lib "eagle-import") (part "R-EU_R0603"))
    )
    (comp (ref "R65")
      (value "1k")
      (footprint "eagle-import:R0603")
      (libsource (lib "eagle-import") (part "R-EU_R0603"))
    )
    (comp (ref "R66")
      (value "1k")
      (footprint "eagle-import:R0603")
      (libsource (lib "eagle-import") (part "R-EU_R0603"))
    )
    (comp (ref "R67")
      (value "2.2k")
      (footprint "eagle-import:R0805")
      (libsource (lib "eagle-import") (part "R-EU_R0805"))
    )
    (comp (ref "R68")
      (value "2.2k")
      (footprint "eagle-import:R0805")
      (libsource (lib "eagle-import") (part "R-EU_R0805"))
    )
    (comp (ref "SJ1") (value "SJ") (footprint "eagle-import:SJ") (libsource (lib "eagle-import") (part "SJ")))
    (comp (ref "U$1")
      (value "TPS562209")
      (footprint "eagle-import:SOT95P280X110-6N")
      (libsource (lib "eagle-import") (part "TPS562209"))
    )
    (comp (ref "U1")
      (value "CD74HC4067SM96")
      (footprint "eagle-import:SOP65P780X200-24N")
      (fields (field (name "MF") "Texas Instruments"))
      (libsource (lib "eagle-import") (part "CD74HC4067SM96"))
    )
    (comp (ref "U2")
      (value "CD74HC4067SM96")
      (footprint "eagle-import:SOP65P780X200-24N")
      (fields (field (name "MF") "Texas Instruments"))
      (libsource (lib "eagle-import") (part "CD74HC4067SM96"))
    )
    (comp (ref "U3")
      (value "CD74HC4067SM96")
      (footprint "eagle-import:SOP65P780X200-24N")
      (fields (field (name "MF") "Texas Instruments"))
      (libsource (lib "eagle-import") (part "CD74HC4067SM96"))
    )
    (comp (ref "U4")
      (value "CD74HC4067SM96")
      (footprint "eagle-import:SOP65P780X200-24N")
      (fields (field (name "MF") "Texas Instruments"))
      (libsource (lib "eagle-import") (part "CD74HC4067SM96"))
    )
    (comp (ref "U5")
      (value "CDCV304PW")
      (footprint "eagle-import:SOP65P640X120-8N")
      (fields (field (name "MF") "Texas Instruments"))
      (libsource (lib "eagle-import") (part "CDCV304PW"))
    )
    (comp (ref "U6")
      (value "CDCV304PW")
      (footprint "eagle-import:SOP65P640X120-8N")
      (fields (field (name "MF") "Texas Instruments"))
      (libsource (lib "eagle-import") (part "CDCV304PW"))
    )
    (comp (ref "U7")
      (value "CDCV304PW")
      (footprint "eagle-import:SOP65P640X120-8N")
      (fields (field (name "MF") "Texas Instruments"))
      (libsource (lib "eagle-import") (part "CDCV304PW"))
    )
    (comp (ref "U8")
      (value "CDCV304PW")
      (footprint "eagle-import:SOP65P640X120-8N")
      (fields (field (name "MF") "Texas Instruments"))
      (libsource (lib "eagle-import") (part "CDCV304PW"))
    )
    (comp (ref "U9")
      (value "SN74LV00ADGVR")
      (footprint "eagle-import:SOP40P640X120-14N")
      (fields (field (name "MF") "Texas Instruments"))
      (libsource (lib "eagle-import") (part "SN74LV00ADGVR"))
    )
    (comp (ref "U10")
      (value "SN74LV00ADGVR")
      (footprint "eagle-import:SOP40P640X120-14N")
      (fields (field (name "MF") "Texas Instruments"))
      (libsource (lib "eagle-import") (part "SN74LV00ADGVR"))
    )
    (comp (ref "U11")
      (value "SN74LV00ADGVR")
      (footprint "eagle-import:SOP40P640X120-14N")
      (fields (field (name "MF") "Texas Instruments"))
      (libsource (lib "eagle-import") (part "SN74LV00ADGVR"))
    )
    (comp (ref "U12")
      (value "SN74LV00ADGVR")
      (footprint "eagle-import:SOP40P640X120-14N")
      (fields (field (name "MF") "Texas Instruments"))
      (libsource (lib "eagle-import") (part "SN74LV00ADGVR"))
    )
    (comp (ref "U13")
      (value "SN74LV00ADGVR")
      (footprint "eagle-import:SOP40P640X120-14N")
      (fields (field (name "MF") "Texas Instruments"))
      (libsource (lib "eagle-import") (part "SN74LV00ADGVR"))
    )
    (comp (ref "U14")
      (value "SN74LV00ADGVR")
      (footprint "eagle-import:SOP40P640X120-14N")
      (fields (field (name "MF") "Texas Instruments"))
      (libsource (lib "eagle-import") (part "SN74LV00ADGVR"))
    )
    (comp (ref "U15")
      (value "SN74LV00ADGVR")
      (footprint "eagle-import:SOP40P640X120-14N")
      (fields (field (name "MF") "Texas Instruments"))
      (libsource (lib "eagle-import") (part "SN74LV00ADGVR"))
    )
    (comp (ref "U16")
      (value "SN74LV00ADGVR")
      (footprint "eagle-import:SOP40P640X120-14N")
      (fields (field (name "MF") "Texas Instruments"))
      (libsource (lib "eagle-import") (part "SN74LV00ADGVR"))
    )
    (comp (ref "U17")
      (value "SN74LV00ADGVR")
      (footprint "eagle-import:SOP40P640X120-14N")
      (fields (field (name "MF") "Texas Instruments"))
      (libsource (lib "eagle-import") (part "SN74LV00ADGVR"))
    )
    (comp (ref "U18")
      (value "SN74LV00ADGVR")
      (footprint "eagle-import:SOP40P640X120-14N")
      (fields (field (name "MF") "Texas Instruments"))
      (libsource (lib "eagle-import") (part "SN74LV00ADGVR"))
    )
    (comp (ref "U19")
      (value "SN74LV00ADGVR")
      (footprint "eagle-import:SOP40P640X120-14N")
      (fields (field (name "MF") "Texas Instruments"))
      (libsource (lib "eagle-import") (part "SN74LV00ADGVR"))
    )
    (comp (ref "U20")
      (value "SN74LV00ADGVR")
      (footprint "eagle-import:SOP40P640X120-14N")
      (fields (field (name "MF") "Texas Instruments"))
      (libsource (lib "eagle-import") (part "SN74LV00ADGVR"))
    )
    (comp (ref "U21")
      (value "SN74LV00ADGVR")
      (footprint "eagle-import:SOP40P640X120-14N")
      (fields (field (name "MF") "Texas Instruments"))
      (libsource (lib "eagle-import") (part "SN74LV00ADGVR"))
    )
    (comp (ref "U22")
      (value "SN74LV00ADGVR")
      (footprint "eagle-import:SOP40P640X120-14N")
      (fields (field (name "MF") "Texas Instruments"))
      (libsource (lib "eagle-import") (part "SN74LV00ADGVR"))
    )
    (comp (ref "U23")
      (value "SN74LV00ADGVR")
      (footprint "eagle-import:SOP40P640X120-14N")
      (fields (field (name "MF") "Texas Instruments"))
      (libsource (lib "eagle-import") (part "SN74LV00ADGVR"))
    )
    (comp (ref "U24")
      (value "SN74LV00ADGVR")
      (footprint "eagle-import:SOP40P640X120-14N")
      (fields (field (name "MF") "Texas Instruments"))
      (libsource (lib "eagle-import") (part "SN74LV00ADGVR"))
    )
  )
  (nets
    (net (code "1") (name "+3V3") (class "Default")
      (node (ref "C1") (pin "1") (pinfunction "1_1") (pintype "passive"))
      (node (ref "C10") (pin "1") (pinfunction "1_1") (pintype "passive"))
      (node (ref "C13") (pin "1") (pinfunction "1_1") (pintype "passive"))
      (node (ref "C14") (pin "1") (pinfunction "1_1") (pintype "passive"))
      (node (ref "C16") (pin "1") (pinfunction "1_1") (pintype "passive"))
      (node (ref "C17") (pin "1") (pinfunction "1_1") (pintype "passive"))
      (node (ref "C18") (pin "1") (pinfunction "1_1") (pintype "passive"))
      (node (ref "C19") (pin "1") (pinfunction "1_1") (pintype "passive"))
      (node (ref "C2") (pin "1") (pinfunction "1_1") (pintype "passive"))
      (node (ref "C20") (pin "1") (pinfunction "1_1") (pintype "passive"))
      (node (ref "C21") (pin "1") (pinfunction "1_1") (pintype "passive"))
      (node (ref "C22") (pin "1") (pinfunction "1_1") (pintype "passive"))
      (node (ref "C23") (pin "1") (pinfunction "1_1") (pintype "passive"))
      (node (ref "C24") (pin "1") (pinfunction "1_1") (pintype "passive"))
      (node (ref "C25") (pin "1") (pinfunction "1_1") (pintype "passive"))
      (node (ref "C26") (pin "1") (pinfunction "1_1") (pintype "passive"))
      (node (ref "C27") (pin "1") (pinfunction "1_1") (pintype "passive"))
      (node (ref "C28") (pin "1") (pinfunction "1_1") (pintype "passive"))
      (node (ref "C29") (pin "1") (pinfunction "1_1") (pintype "passive"))
      (node (ref "C3") (pin "1") (pinfunction "1_1") (pintype "passive"))
      (node (ref "C30") (pin "1") (pinfunction "1_1") (pintype "passive"))
      (node (ref "C31") (pin "1") (pinfunction "1_1") (pintype "passive"))
      (node (ref "C4") (pin "1") (pinfunction "1_1") (pintype "passive"))
      (node (ref "C5") (pin "1") (pinfunction "1_1") (pintype "passive"))
      (node (ref "C6") (pin "1") (pinfunction "1_1") (pintype "passive"))
      (node (ref "C7") (pin "1") (pinfunction "1_1") (pintype "passive"))
      (node (ref "C8") (pin "1") (pinfunction "1_1") (pintype "passive"))
      (node (ref "C9") (pin "2") (pinfunction "2_2") (pintype "passive"))
      (node (ref "CRYSTAL") (pin "1") (pinfunction "O/E_1") (pintype "input"))
      (node (ref "CRYSTAL") (pin "6") (pinfunction "+VDC_6") (pintype "input"))
      (node (ref "J1") (pin "1") (pinfunction "1_1") (pintype "passive"))
      (node (ref "J17") (pin "1") (pinfunction "1_1") (pintype "passive"))
      (node (ref "J18") (pin "1") (pinfunction "1_1") (pintype "passive"))
      (node (ref "J19") (pin "1") (pinfunction "1_1") (pintype "passive"))
      (node (ref "J20") (pin "1") (pinfunction "1_1") (pintype "passive"))
      (node (ref "J4") (pin "1") (pinfunction "1_1") (pintype "passive"))
      (node (ref "J5") (pin "1") (pinfunction "1_1") (pintype "passive"))
      (node (ref "J8") (pin "1") (pinfunction "1_1") (pintype "passive"))
      (node (ref "L1") (pin "2") (pinfunction "2_2") (pintype "passive"))
      (node (ref "MUX") (pin "13") (pinfunction "AN_13") (pintype "bidirectional"))
      (node (ref "MUX") (pin "16") (pinfunction "VCC_16") (pintype "bidirectional"))
      (node (ref "MUX") (pin "3") (pinfunction "BN_3") (pintype "bidirectional"))
      (node (ref "R1") (pin "2") (pinfunction "2_2") (pintype "passive"))
      (node (ref "SJ1") (pin "2") (pinfunction "2_2") (pintype "passive"))
      (node (ref "U1") (pin "24") (pinfunction "VCC_24") (pintype "power_in"))
      (node (ref "U10") (pin "14") (pinfunction "VCC_14") (pintype "power_in"))
      (node (ref "U11") (pin "14") (pinfunction "VCC_14") (pintype "power_in"))
      (node (ref "U12") (pin "14") (pinfunction "VCC_14") (pintype "power_in"))
      (node (ref "U13") (pin "14") (pinfunction "VCC_14") (pintype "power_in"))
      (node (ref "U14") (pin "14") (pinfunction "VCC_14") (pintype "power_in"))
      (node (ref "U15") (pin "14") (pinfunction "VCC_14") (pintype "power_in"))
      (node (ref "U16") (pin "14") (pinfunction "VCC_14") (pintype "power_in"))
      (node (ref "U17") (pin "14") (pinfunction "VCC_14") (pintype "power_in"))
      (node (ref "U18") (pin "14") (pinfunction "VCC_14") (pintype "power_in"))
      (node (ref "U19") (pin "14") (pinfunction "VCC_14") (pintype "power_in"))
      (node (ref "U2") (pin "24") (pinfunction "VCC_24") (pintype "power_in"))
      (node (ref "U20") (pin "14") (pinfunction "VCC_14") (pintype "power_in"))
      (node (ref "U21") (pin "14") (pinfunction "VCC_14") (pintype "power_in"))
      (node (ref "U22") (pin "14") (pinfunction "VCC_14") (pintype "power_in"))
      (node (ref "U23") (pin "14") (pinfunction "VCC_14") (pintype "power_in"))
      (node (ref "U24") (pin "14") (pinfunction "VCC_14") (pintype "power_in"))
      (node (ref "U3") (pin "24") (pinfunction "VCC_24") (pintype "power_in"))
      (node (ref "U4") (pin "24") (pinfunction "VCC_24") (pintype "power_in"))
      (node (ref "U5") (pin "2") (pinfunction "OE_2") (pintype "input"))
      (node (ref "U5") (pin "6") (pinfunction "VDD_6") (pintype "power_in"))
      (node (ref "U6") (pin "2") (pinfunction "OE_2") (pintype "input"))
      (node (ref "U6") (pin "6") (pinfunction "VDD_6") (pintype "power_in"))
      (node (ref "U7") (pin "2") (pinfunction "OE_2") (pintype "input"))
      (node (ref "U7") (pin "6") (pinfunction "VDD_6") (pintype "power_in"))
      (node (ref "U8") (pin "2") (pinfunction "OE_2") (pintype "input"))
      (node (ref "U8") (pin "6") (pinfunction "VDD_6") (pintype "power_in"))
      (node (ref "U9") (pin "14") (pinfunction "VCC_14") (pintype "power_in"))
    )
    (net (code "2") (name "/A0_A") (class "Default")
      (node (ref "MUX") (pin "12") (pinfunction "A0_12") (pintype "bidirectional"))
      (node (ref "U1") (pin "1") (pinfunction "COMMON_IN/OUT_1") (pintype "bidirectional"))
    )
    (net (code "3") (name "/A1_A") (class "Default")
      (node (ref "MUX") (pin "14") (pinfunction "A1_14") (pintype "bidirectional"))
      (node (ref "U2") (pin "1") (pinfunction "COMMON_IN/OUT_1") (pintype "bidirectional"))
    )
    (net (code "4") (name "/A2_A") (class "Default")
      (node (ref "MUX") (pin "15") (pinfunction "A2_15") (pintype "bidirectional"))
      (node (ref "U3") (pin "1") (pinfunction "COMMON_IN/OUT_1") (pintype "bidirectional"))
    )
    (net (code "5") (name "/A3_A") (class "Default")
      (node (ref "MUX") (pin "11") (pinfunction "A3_11") (pintype "bidirectional"))
      (node (ref "U4") (pin "1") (pinfunction "COMMON_IN/OUT_1") (pintype "bidirectional"))
    )
    (net (code "6") (name "/B0_A") (class "Default")
      (node (ref "MUX") (pin "1") (pinfunction "B0_1") (pintype "bidirectional"))
    )
    (net (code "7") (name "/B1_A") (class "Default")
      (node (ref "MUX") (pin "5") (pinfunction "B1_5") (pintype "bidirectional"))
    )
    (net (code "8") (name "/B2_A") (class "Default")
      (node (ref "MUX") (pin "2") (pinfunction "B2_2") (pintype "bidirectional"))
    )
    (net (code "9") (name "/B3_A") (class "Default")
      (node (ref "MUX") (pin "4") (pinfunction "B3_4") (pintype "bidirectional"))
    )
    (net (code "10") (name "/DIN_2") (class "Default")
      (node (ref "CN7") (pin "8") (pinfunction "8_8") (pintype "passive"))
      (node (ref "J1") (pin "12") (pinfunction "12_12") (pintype "passive"))
      (node (ref "J17") (pin "12") (pinfunction "12_12") (pintype "passive"))
      (node (ref "J18") (pin "12") (pinfunction "12_12") (pintype "passive"))
      (node (ref "J2") (pin "10") (pinfunction "10_10") (pintype "passive"))
      (node (ref "J3") (pin "10") (pinfunction "10_10") (pintype "passive"))
      (node (ref "J4") (pin "12") (pinfunction "12_12") (pintype "passive"))
      (node (ref "J6") (pin "10") (pinfunction "10_10") (pintype "passive"))
      (node (ref "J7") (pin "10") (pinfunction "10_10") (pintype "passive"))
    )
    (net (code "11") (name "/DIN_5") (class "Default")
      (node (ref "CN9") (pin "8") (pinfunction "8_8") (pintype "passive"))
      (node (ref "J10") (pin "10") (pinfunction "10_10") (pintype "passive"))
      (node (ref "J11") (pin "10") (pinfunction "10_10") (pintype "passive"))
      (node (ref "J14") (pin "10") (pinfunction "10_10") (pintype "passive"))
      (node (ref "J15") (pin "10") (pinfunction "10_10") (pintype "passive"))
      (node (ref "J19") (pin "12") (pinfunction "12_12") (pintype "passive"))
      (node (ref "J20") (pin "12") (pinfunction "12_12") (pintype "passive"))
      (node (ref "J5") (pin "12") (pinfunction "12_12") (pintype "passive"))
      (node (ref "J8") (pin "12") (pinfunction "12_12") (pintype "passive"))
    )
    (net (code "12") (name "/FSELECT") (class "Default")
      (node (ref "CN10") (pin "8") (pinfunction "8_8") (pintype "passive"))
      (node (ref "J1") (pin "3") (pinfunction "3_3") (pintype "passive"))
      (node (ref "J10") (pin "1") (pinfunction "1_1") (pintype "passive"))
      (node (ref "J11") (pin "1") (pinfunction "1_1") (pintype "passive"))
      (node (ref "J14") (pin "1") (pinfunction "1_1") (pintype "passive"))
      (node (ref "J15") (pin "1") (pinfunction "1_1") (pintype "passive"))
      (node (ref "J17") (pin "3") (pinfunction "3_3") (pintype "passive"))
      (node (ref "J18") (pin "3") (pinfunction "3_3") (pintype "passive"))
      (node (ref "J19") (pin "3") (pinfunction "3_3") (pintype "passive"))
      (node (ref "J2") (pin "1") (pinfunction "1_1") (pintype "passive"))
      (node (ref "J20") (pin "3") (pinfunction "3_3") (pintype "passive"))
      (node (ref "J3") (pin "1") (pinfunction "1_1") (pintype "passive"))
      (node (ref "J4") (pin "3") (pinfunction "3_3") (pintype "passive"))
      (node (ref "J5") (pin "3") (pinfunction "3_3") (pintype "passive"))
      (node (ref "J6") (pin "1") (pinfunction "1_1") (pintype "passive"))
      (node (ref "J7") (pin "1") (pinfunction "1_1") (pintype "passive"))
      (node (ref "J8") (pin "3") (pinfunction "3_3") (pintype "passive"))
    )
    (net (code "13") (name "/FSYNC1_A") (class "Default")
      (node (ref "J17") (pin "5") (pinfunction "5_5") (pintype "passive"))
      (node (ref "U9") (pin "3") (pinfunction "1Y_3") (pintype "output"))
    )
    (net (code "14") (name "/FSYNC1_B") (class "Default")
      (node (ref "J4") (pin "5") (pinfunction "5_5") (pintype "passive"))
      (node (ref "U13") (pin "3") (pinfunction "1Y_3") (pintype "output"))
    )
    (net (code "15") (name "/FSYNC1_C") (class "Default")
      (node (ref "J19") (pin "5") (pinfunction "5_5") (pintype "passive"))
      (node (ref "U17") (pin "3") (pinfunction "1Y_3") (pintype "output"))
    )
    (net (code "16") (name "/FSYNC1_D") (class "Default")
      (node (ref "J5") (pin "5") (pinfunction "5_5") (pintype "passive"))
      (node (ref "U21") (pin "3") (pinfunction "1Y_3") (pintype "output"))
    )
    (net (code "17") (name "/FSYNC2_A") (class "Default")
      (node (ref "J17") (pin "8") (pinfunction "8_8") (pintype "passive"))
      (node (ref "U9") (pin "6") (pinfunction "2Y_6") (pintype "output"))
    )
    (net (code "18") (name "/FSYNC2_B") (class "Default")
      (node (ref "J4") (pin "8") (pinfunction "8_8") (pintype "passive"))
      (node (ref "U13") (pin "6") (pinfunction "2Y_6") (pintype "output"))
    )
    (net (code "19") (name "/FSYNC2_C") (class "Default")
      (node (ref "J19") (pin "8") (pinfunction "8_8") (pintype "passive"))
      (node (ref "U17") (pin "6") (pinfunction "2Y_6") (pintype "output"))
    )
    (net (code "20") (name "/FSYNC2_D") (class "Default")
      (node (ref "J5") (pin "8") (pinfunction "8_8") (pintype "passive"))
      (node (ref "U21") (pin "6") (pinfunction "2Y_6") (pintype "output"))
    )
    (net (code "21") (name "/FSYNC3_A") (class "Default")
      (node (ref "J17") (pin "7") (pinfunction "7_7") (pintype "passive"))
      (node (ref "U9") (pin "8") (pinfunction "3Y_8") (pintype "output"))
    )
    (net (code "22") (name "/FSYNC3_B") (class "Default")
      (node (ref "J4") (pin "7") (pinfunction "7_7") (pintype "passive"))
      (node (ref "U13") (pin "8") (pinfunction "3Y_8") (pintype "output"))
    )
    (net (code "23") (name "/FSYNC3_C") (class "Default")
      (node (ref "J19") (pin "7") (pinfunction "7_7") (pintype "passive"))
      (node (ref "U17") (pin "8") (pinfunction "3Y_8") (pintype "output"))
    )
    (net (code "24") (name "/FSYNC3_D") (class "Default")
      (node (ref "J5") (pin "7") (pinfunction "7_7") (pintype "passive"))
      (node (ref "U21") (pin "8") (pinfunction "3Y_8") (pintype "output"))
    )
    (net (code "25") (name "/FSYNC4_A") (class "Default")
      (node (ref "J17") (pin "10") (pinfunction "10_10") (pintype "passive"))
      (node (ref "U9") (pin "11") (pinfunction "4Y_11") (pintype "output"))
    )
    (net (code "26") (name "/FSYNC4_B") (class "Default")
      (node (ref "J4") (pin "10") (pinfunction "10_10") (pintype "passive"))
      (node (ref "U13") (pin "11") (pinfunction "4Y_11") (pintype "output"))
    )
    (net (code "27") (name "/FSYNC4_C") (class "Default")
      (node (ref "J19") (pin "10") (pinfunction "10_10") (pintype "passive"))
      (node (ref "U17") (pin "11") (pinfunction "4Y_11") (pintype "output"))
    )
    (net (code "28") (name "/FSYNC4_D") (class "Default")
      (node (ref "J5") (pin "10") (pinfunction "10_10") (pintype "passive"))
      (node (ref "U21") (pin "11") (pinfunction "4Y_11") (pintype "output"))
    )
    (net (code "29") (name "/FSYNC5_A") (class "Default")
      (node (ref "J2") (pin "3") (pinfunction "3_3") (pintype "passive"))
      (node (ref "U10") (pin "3") (pinfunction "1Y_3") (pintype "output"))
    )
    (net (code "30") (name "/FSYNC5_B") (class "Default")
      (node (ref "J6") (pin "3") (pinfunction "3_3") (pintype "passive"))
      (node (ref "U14") (pin "3") (pinfunction "1Y_3") (pintype "output"))
    )
    (net (code "31") (name "/FSYNC5_C") (class "Default")
      (node (ref "J10") (pin "3") (pinfunction "3_3") (pintype "passive"))
      (node (ref "U18") (pin "3") (pinfunction "1Y_3") (pintype "output"))
    )
    (net (code "32") (name "/FSYNC5_D") (class "Default")
      (node (ref "J14") (pin "3") (pinfunction "3_3") (pintype "passive"))
      (node (ref "U22") (pin "3") (pinfunction "1Y_3") (pintype "output"))
    )
    (net (code "33") (name "/FSYNC6_A") (class "Default")
      (node (ref "J2") (pin "6") (pinfunction "6_6") (pintype "passive"))
      (node (ref "U10") (pin "6") (pinfunction "2Y_6") (pintype "output"))
    )
    (net (code "34") (name "/FSYNC6_B") (class "Default")
      (node (ref "J6") (pin "6") (pinfunction "6_6") (pintype "passive"))
      (node (ref "U14") (pin "6") (pinfunction "2Y_6") (pintype "output"))
    )
    (net (code "35") (name "/FSYNC6_C") (class "Default")
      (node (ref "J10") (pin "6") (pinfunction "6_6") (pintype "passive"))
      (node (ref "U18") (pin "6") (pinfunction "2Y_6") (pintype "output"))
    )
    (net (code "36") (name "/FSYNC6_D") (class "Default")
      (node (ref "J14") (pin "6") (pinfunction "6_6") (pintype "passive"))
      (node (ref "U22") (pin "6") (pinfunction "2Y_6") (pintype "output"))
    )
    (net (code "37") (name "/FSYNC7_A") (class "Default")
      (node (ref "J2") (pin "5") (pinfunction "5_5") (pintype "passive"))
      (node (ref "U10") (pin "8") (pinfunction "3Y_8") (pintype "output"))
    )
    (net (code "38") (name "/FSYNC7_B") (class "Default")
      (node (ref "J6") (pin "5") (pinfunction "5_5") (pintype "passive"))
      (node (ref "U14") (pin "8") (pinfunction "3Y_8") (pintype "output"))
    )
    (net (code "39") (name "/FSYNC7_C") (class "Default")
      (node (ref "J10") (pin "5") (pinfunction "5_5") (pintype "passive"))
      (node (ref "U18") (pin "8") (pinfunction "3Y_8") (pintype "output"))
    )
    (net (code "40") (name "/FSYNC7_D") (class "Default")
      (node (ref "J14") (pin "5") (pinfunction "5_5") (pintype "passive"))
      (node (ref "U22") (pin "8") (pinfunction "3Y_8") (pintype "output"))
    )
    (net (code "41") (name "/FSYNC8_A") (class "Default")
      (node (ref "J2") (pin "8") (pinfunction "8_8") (pintype "passive"))
      (node (ref "U10") (pin "11") (pinfunction "4Y_11") (pintype "output"))
    )
    (net (code "42") (name "/FSYNC8_B") (class "Default")
      (node (ref "J6") (pin "8") (pinfunction "8_8") (pintype "passive"))
      (node (ref "U14") (pin "11") (pinfunction "4Y_11") (pintype "output"))
    )
    (net (code "43") (name "/FSYNC8_C") (class "Default")
      (node (ref "J10") (pin "8") (pinfunction "8_8") (pintype "passive"))
      (node (ref "U18") (pin "11") (pinfunction "4Y_11") (pintype "output"))
    )
    (net (code "44") (name "/FSYNC8_D") (class "Default")
      (node (ref "J14") (pin "8") (pinfunction "8_8") (pintype "passive"))
      (node (ref "U22") (pin "11") (pinfunction "4Y_11") (pintype "output"))
    )
    (net (code "45") (name "/FSYNC9_A") (class "Default")
      (node (ref "J3") (pin "3") (pinfunction "3_3") (pintype "passive"))
      (node (ref "U11") (pin "3") (pinfunction "1Y_3") (pintype "output"))
    )
    (net (code "46") (name "/FSYNC9_B") (class "Default")
      (node (ref "J7") (pin "3") (pinfunction "3_3") (pintype "passive"))
      (node (ref "U15") (pin "3") (pinfunction "1Y_3") (pintype "output"))
    )
    (net (code "47") (name "/FSYNC9_C") (class "Default")
      (node (ref "J11") (pin "3") (pinfunction "3_3") (pintype "passive"))
      (node (ref "U19") (pin "3") (pinfunction "1Y_3") (pintype "output"))
    )
    (net (code "48") (name "/FSYNC9_D") (class "Default")
      (node (ref "J15") (pin "3") (pinfunction "3_3") (pintype "passive"))
      (node (ref "U23") (pin "3") (pinfunction "1Y_3") (pintype "output"))
    )
    (net (code "49") (name "/FSYNC10_A") (class "Default")
      (node (ref "J3") (pin "6") (pinfunction "6_6") (pintype "passive"))
      (node (ref "U11") (pin "6") (pinfunction "2Y_6") (pintype "output"))
    )
    (net (code "50") (name "/FSYNC10_B") (class "Default")
      (node (ref "J7") (pin "6") (pinfunction "6_6") (pintype "passive"))
      (node (ref "U15") (pin "6") (pinfunction "2Y_6") (pintype "output"))
    )
    (net (code "51") (name "/FSYNC10_C") (class "Default")
      (node (ref "J11") (pin "6") (pinfunction "6_6") (pintype "passive"))
      (node (ref "U19") (pin "6") (pinfunction "2Y_6") (pintype "output"))
    )
    (net (code "52") (name "/FSYNC10_D") (class "Default")
      (node (ref "J15") (pin "6") (pinfunction "6_6") (pintype "passive"))
      (node (ref "U23") (pin "6") (pinfunction "2Y_6") (pintype "output"))
    )
    (net (code "53") (name "/FSYNC11_A") (class "Default")
      (node (ref "J3") (pin "5") (pinfunction "5_5") (pintype "passive"))
      (node (ref "U11") (pin "8") (pinfunction "3Y_8") (pintype "output"))
    )
    (net (code "54") (name "/FSYNC11_B") (class "Default")
      (node (ref "J7") (pin "5") (pinfunction "5_5") (pintype "passive"))
      (node (ref "U15") (pin "8") (pinfunction "3Y_8") (pintype "output"))
    )
    (net (code "55") (name "/FSYNC11_C") (class "Default")
      (node (ref "J11") (pin "5") (pinfunction "5_5") (pintype "passive"))
      (node (ref "U19") (pin "8") (pinfunction "3Y_8") (pintype "output"))
    )
    (net (code "56") (name "/FSYNC11_D") (class "Default")
      (node (ref "J15") (pin "5") (pinfunction "5_5") (pintype "passive"))
      (node (ref "U23") (pin "8") (pinfunction "3Y_8") (pintype "output"))
    )
    (net (code "57") (name "/FSYNC12_A") (class "Default")
      (node (ref "J3") (pin "8") (pinfunction "8_8") (pintype "passive"))
      (node (ref "U11") (pin "11") (pinfunction "4Y_11") (pintype "output"))
    )
    (net (code "58") (name "/FSYNC12_B") (class "Default")
      (node (ref "J7") (pin "8") (pinfunction "8_8") (pintype "passive"))
      (node (ref "U15") (pin "11") (pinfunction "4Y_11") (pintype "output"))
    )
    (net (code "59") (name "/FSYNC12_C") (class "Default")
      (node (ref "J11") (pin "8") (pinfunction "8_8") (pintype "passive"))
      (node (ref "U19") (pin "11") (pinfunction "4Y_11") (pintype "output"))
    )
    (net (code "60") (name "/FSYNC12_D") (class "Default")
      (node (ref "J15") (pin "8") (pinfunction "8_8") (pintype "passive"))
      (node (ref "U23") (pin "11") (pinfunction "4Y_11") (pintype "output"))
    )
    (net (code "61") (name "/FSYNC13_A") (class "Default")
      (node (ref "J1") (pin "5") (pinfunction "5_5") (pintype "passive"))
      (node (ref "U12") (pin "3") (pinfunction "1Y_3") (pintype "output"))
    )
    (net (code "62") (name "/FSYNC13_B") (class "Default")
      (node (ref "J18") (pin "5") (pinfunction "5_5") (pintype "passive"))
      (node (ref "U16") (pin "3") (pinfunction "1Y_3") (pintype "output"))
    )
    (net (code "63") (name "/FSYNC13_C") (class "Default")
      (node (ref "J20") (pin "5") (pinfunction "5_5") (pintype "passive"))
      (node (ref "U20") (pin "3") (pinfunction "1Y_3") (pintype "output"))
    )
    (net (code "64") (name "/FSYNC13_D") (class "Default")
      (node (ref "J8") (pin "5") (pinfunction "5_5") (pintype "passive"))
      (node (ref "U24") (pin "3") (pinfunction "1Y_3") (pintype "output"))
    )
    (net (code "65") (name "/FSYNC14_A") (class "Default")
      (node (ref "J1") (pin "8") (pinfunction "8_8") (pintype "passive"))
      (node (ref "U12") (pin "6") (pinfunction "2Y_6") (pintype "output"))
    )
    (net (code "66") (name "/FSYNC14_B") (class "Default")
      (node (ref "J18") (pin "8") (pinfunction "8_8") (pintype "passive"))
      (node (ref "U16") (pin "6") (pinfunction "2Y_6") (pintype "output"))
    )
    (net (code "67") (name "/FSYNC14_C") (class "Default")
      (node (ref "J20") (pin "8") (pinfunction "8_8") (pintype "passive"))
      (node (ref "U20") (pin "6") (pinfunction "2Y_6") (pintype "output"))
    )
    (net (code "68") (name "/FSYNC14_D") (class "Default")
      (node (ref "J8") (pin "8") (pinfunction "8_8") (pintype "passive"))
      (node (ref "U24") (pin "6") (pinfunction "2Y_6") (pintype "output"))
    )
    (net (code "69") (name "/FSYNC15_A") (class "Default")
      (node (ref "J1") (pin "7") (pinfunction "7_7") (pintype "passive"))
      (node (ref "U12") (pin "8") (pinfunction "3Y_8") (pintype "output"))
    )
    (net (code "70") (name "/FSYNC15_B") (class "Default")
      (node (ref "J18") (pin "7") (pinfunction "7_7") (pintype "passive"))
      (node (ref "U16") (pin "8") (pinfunction "3Y_8") (pintype "output"))
    )
    (net (code "71") (name "/FSYNC15_C") (class "Default")
      (node (ref "J20") (pin "7") (pinfunction "7_7") (pintype "passive"))
      (node (ref "U20") (pin "8") (pinfunction "3Y_8") (pintype "output"))
    )
    (net (code "72") (name "/FSYNC15_D") (class "Default")
      (node (ref "J8") (pin "7") (pinfunction "7_7") (pintype "passive"))
      (node (ref "U24") (pin "8") (pinfunction "3Y_8") (pintype "output"))
    )
    (net (code "73") (name "/FSYNC16_A") (class "Default")
      (node (ref "J1") (pin "10") (pinfunction "10_10") (pintype "passive"))
      (node (ref "U12") (pin "11") (pinfunction "4Y_11") (pintype "output"))
    )
    (net (code "74") (name "/FSYNC16_B") (class "Default")
      (node (ref "J18") (pin "10") (pinfunction "10_10") (pintype "passive"))
      (node (ref "U16") (pin "11") (pinfunction "4Y_11") (pintype "output"))
    )
    (net (code "75") (name "/FSYNC16_C") (class "Default")
      (node (ref "J20") (pin "10") (pinfunction "10_10") (pintype "passive"))
      (node (ref "U20") (pin "11") (pinfunction "4Y_11") (pintype "output"))
    )
    (net (code "76") (name "/FSYNC16_D") (class "Default")
      (node (ref "J8") (pin "10") (pinfunction "10_10") (pintype "passive"))
      (node (ref "U24") (pin "11") (pinfunction "4Y_11") (pintype "output"))
    )
    (net (code "77") (name "/I0_A") (class "Default")
      (node (ref "R3") (pin "2") (pinfunction "2_2") (pintype "passive"))
      (node (ref "U1") (pin "9") (pinfunction "I0_9") (pintype "input"))
      (node (ref "U9") (pin "1") (pinfunction "1A_1") (pintype "input"))
      (node (ref "U9") (pin "2") (pinfunction "1B_2") (pintype "input"))
    )
    (net (code "78") (name "/I0_B") (class "Default")
      (node (ref "R19") (pin "2") (pinfunction "2_2") (pintype "passive"))
      (node (ref "U13") (pin "1") (pinfunction "1A_1") (pintype "input"))
      (node (ref "U13") (pin "2") (pinfunction "1B_2") (pintype "input"))
      (node (ref "U2") (pin "9") (pinfunction "I0_9") (pintype "input"))
    )
    (net (code "79") (name "/I0_C") (class "Default")
      (node (ref "R35") (pin "2") (pinfunction "2_2") (pintype "passive"))
      (node (ref "U17") (pin "1") (pinfunction "1A_1") (pintype "input"))
      (node (ref "U17") (pin "2") (pinfunction "1B_2") (pintype "input"))
      (node (ref "U3") (pin "9") (pinfunction "I0_9") (pintype "input"))
    )
    (net (code "80") (name "/I0_D") (class "Default")
      (node (ref "R51") (pin "2") (pinfunction "2_2") (pintype "passive"))
      (node (ref "U21") (pin "1") (pinfunction "1A_1") (pintype "input"))
      (node (ref "U21") (pin "2") (pinfunction "1B_2") (pintype "input"))
      (node (ref "U4") (pin "9") (pinfunction "I0_9") (pintype "input"))
    )
    (net (code "81") (name "/I1_A") (class "Default")
      (node (ref "R4") (pin "2") (pinfunction "2_2") (pintype "passive"))
      (node (ref "U1") (pin "8") (pinfunction "I1_8") (pintype "input"))
      (node (ref "U9") (pin "4") (pinfunction "2A_4") (pintype "input"))
      (node (ref "U9") (pin "5") (pinfunction "2B_5") (pintype "input"))
    )
    (net (code "82") (name "/I1_B") (class "Default")
      (node (ref "R20") (pin "2") (pinfunction "2_2") (pintype "passive"))
      (node (ref "U13") (pin "4") (pinfunction "2A_4") (pintype "input"))
      (node (ref "U13") (pin "5") (pinfunction "2B_5") (pintype "input"))
      (node (ref "U2") (pin "8") (pinfunction "I1_8") (pintype "input"))
    )
    (net (code "83") (name "/I1_C") (class "Default")
      (node (ref "R36") (pin "2") (pinfunction "2_2") (pintype "passive"))
      (node (ref "U17") (pin "4") (pinfunction "2A_4") (pintype "input"))
      (node (ref "U17") (pin "5") (pinfunction "2B_5") (pintype "input"))
      (node (ref "U3") (pin "8") (pinfunction "I1_8") (pintype "input"))
    )
    (net (code "84") (name "/I1_D") (class "Default")
      (node (ref "R52") (pin "2") (pinfunction "2_2") (pintype "passive"))
      (node (ref "U21") (pin "4") (pinfunction "2A_4") (pintype "input"))
      (node (ref "U21") (pin "5") (pinfunction "2B_5") (pintype "input"))
      (node (ref "U4") (pin "8") (pinfunction "I1_8") (pintype "input"))
    )
    (net (code "85") (name "/I2_A") (class "Default")
      (node (ref "R5") (pin "2") (pinfunction "2_2") (pintype "passive"))
      (node (ref "U1") (pin "7") (pinfunction "I2_7") (pintype "input"))
      (node (ref "U9") (pin "10") (pinfunction "3B_10") (pintype "input"))
      (node (ref "U9") (pin "9") (pinfunction "3A_9") (pintype "input"))
    )
    (net (code "86") (name "/I2_B") (class "Default")
      (node (ref "R21") (pin "2") (pinfunction "2_2") (pintype "passive"))
      (node (ref "U13") (pin "10") (pinfunction "3B_10") (pintype "input"))
      (node (ref "U13") (pin "9") (pinfunction "3A_9") (pintype "input"))
      (node (ref "U2") (pin "7") (pinfunction "I2_7") (pintype "input"))
    )
    (net (code "87") (name "/I2_C") (class "Default")
      (node (ref "R37") (pin "2") (pinfunction "2_2") (pintype "passive"))
      (node (ref "U17") (pin "10") (pinfunction "3B_10") (pintype "input"))
      (node (ref "U17") (pin "9") (pinfunction "3A_9") (pintype "input"))
      (node (ref "U3") (pin "7") (pinfunction "I2_7") (pintype "input"))
    )
    (net (code "88") (name "/I2_D") (class "Default")
      (node (ref "R53") (pin "2") (pinfunction "2_2") (pintype "passive"))
      (node (ref "U21") (pin "10") (pinfunction "3B_10") (pintype "input"))
      (node (ref "U21") (pin "9") (pinfunction "3A_9") (pintype "input"))
      (node (ref "U4") (pin "7") (pinfunction "I2_7") (pintype "input"))
    )
    (net (code "89") (name "/I3_A") (class "Default")
      (node (ref "R6") (pin "2") (pinfunction "2_2") (pintype "passive"))
      (node (ref "U1") (pin "6") (pinfunction "I3_6") (pintype "input"))
      (node (ref "U9") (pin "12") (pinfunction "4A_12") (pintype "input"))
      (node (ref "U9") (pin "13") (pinfunction "4B_13") (pintype "input"))
    )
    (net (code "90") (name "/I3_B") (class "Default")
      (node (ref "R22") (pin "2") (pinfunction "2_2") (pintype "passive"))
      (node (ref "U13") (pin "12") (pinfunction "4A_12") (pintype "input"))
      (node (ref "U13") (pin "13") (pinfunction "4B_13") (pintype "input"))
      (node (ref "U2") (pin "6") (pinfunction "I3_6") (pintype "input"))
    )
    (net (code "91") (name "/I3_C") (class "Default")
      (node (ref "R38") (pin "2") (pinfunction "2_2") (pintype "passive"))
      (node (ref "U17") (pin "12") (pinfunction "4A_12") (pintype "input"))
      (node (ref "U17") (pin "13") (pinfunction "4B_13") (pintype "input"))
      (node (ref "U3") (pin "6") (pinfunction "I3_6") (pintype "input"))
    )
    (net (code "92") (name "/I3_D") (class "Default")
      (node (ref "R54") (pin "2") (pinfunction "2_2") (pintype "passive"))
      (node (ref "U21") (pin "12") (pinfunction "4A_12") (pintype "input"))
      (node (ref "U21") (pin "13") (pinfunction "4B_13") (pintype "input"))
      (node (ref "U4") (pin "6") (pinfunction "I3_6") (pintype "input"))
    )
    (net (code "93") (name "/I4_A") (class "Default")
      (node (ref "R7") (pin "2") (pinfunction "2_2") (pintype "passive"))
      (node (ref "U1") (pin "5") (pinfunction "I4_5") (pintype "input"))
      (node (ref "U10") (pin "1") (pinfunction "1A_1") (pintype "input"))
      (node (ref "U10") (pin "2") (pinfunction "1B_2") (pintype "input"))
    )
    (net (code "94") (name "/I4_B") (class "Default")
      (node (ref "R23") (pin "2") (pinfunction "2_2") (pintype "passive"))
      (node (ref "U14") (pin "1") (pinfunction "1A_1") (pintype "input"))
      (node (ref "U14") (pin "2") (pinfunction "1B_2") (pintype "input"))
      (node (ref "U2") (pin "5") (pinfunction "I4_5") (pintype "input"))
    )
    (net (code "95") (name "/I4_C") (class "Default")
      (node (ref "R39") (pin "2") (pinfunction "2_2") (pintype "passive"))
      (node (ref "U18") (pin "1") (pinfunction "1A_1") (pintype "input"))
      (node (ref "U18") (pin "2") (pinfunction "1B_2") (pintype "input"))
      (node (ref "U3") (pin "5") (pinfunction "I4_5") (pintype "input"))
    )
    (net (code "96") (name "/I4_D") (class "Default")
      (node (ref "R55") (pin "2") (pinfunction "2_2") (pintype "passive"))
      (node (ref "U22") (pin "1") (pinfunction "1A_1") (pintype "input"))
      (node (ref "U22") (pin "2") (pinfunction "1B_2") (pintype "input"))
      (node (ref "U4") (pin "5") (pinfunction "I4_5") (pintype "input"))
    )
    (net (code "97") (name "/I5_A") (class "Default")
      (node (ref "R8") (pin "2") (pinfunction "2_2") (pintype "passive"))
      (node (ref "U1") (pin "4") (pinfunction "I5_4") (pintype "input"))
      (node (ref "U10") (pin "4") (pinfunction "2A_4") (pintype "input"))
      (node (ref "U10") (pin "5") (pinfunction "2B_5") (pintype "input"))
    )
    (net (code "98") (name "/I5_B") (class "Default")
      (node (ref "R24") (pin "2") (pinfunction "2_2") (pintype "passive"))
      (node (ref "U14") (pin "4") (pinfunction "2A_4") (pintype "input"))
      (node (ref "U14") (pin "5") (pinfunction "2B_5") (pintype "input"))
      (node (ref "U2") (pin "4") (pinfunction "I5_4") (pintype "input"))
    )
    (net (code "99") (name "/I5_C") (class "Default")
      (node (ref "R40") (pin "2") (pinfunction "2_2") (pintype "passive"))
      (node (ref "U18") (pin "4") (pinfunction "2A_4") (pintype "input"))
      (node (ref "U18") (pin "5") (pinfunction "2B_5") (pintype "input"))
      (node (ref "U3") (pin "4") (pinfunction "I5_4") (pintype "input"))
    )
    (net (code "100") (name "/I5_D") (class "Default")
      (node (ref "R56") (pin "2") (pinfunction "2_2") (pintype "passive"))
      (node (ref "U22") (pin "4") (pinfunction "2A_4") (pintype "input"))
      (node (ref "U22") (pin "5") (pinfunction "2B_5") (pintype "input"))
      (node (ref "U4") (pin "4") (pinfunction "I5_4") (pintype "input"))
    )
    (net (code "101") (name "/I6_A") (class "Default")
      (node (ref "R9") (pin "2") (pinfunction "2_2") (pintype "passive"))
      (node (ref "U1") (pin "3") (pinfunction "I6_3") (pintype "input"))
      (node (ref "U10") (pin "10") (pinfunction "3B_10") (pintype "input"))
      (node (ref "U10") (pin "9") (pinfunction "3A_9") (pintype "input"))
    )
    (net (code "102") (name "/I6_B") (class "Default")
      (node (ref "R25") (pin "2") (pinfunction "2_2") (pintype "passive"))
      (node (ref "U14") (pin "10") (pinfunction "3B_10") (pintype "input"))
      (node (ref "U14") (pin "9") (pinfunction "3A_9") (pintype "input"))
      (node (ref "U2") (pin "3") (pinfunction "I6_3") (pintype "input"))
    )
    (net (code "103") (name "/I6_C") (class "Default")
      (node (ref "R41") (pin "2") (pinfunction "2_2") (pintype "passive"))
      (node (ref "U18") (pin "10") (pinfunction "3B_10") (pintype "input"))
      (node (ref "U18") (pin "9") (pinfunction "3A_9") (pintype "input"))
      (node (ref "U3") (pin "3") (pinfunction "I6_3") (pintype "input"))
    )
    (net (code "104") (name "/I6_D") (class "Default")
      (node (ref "R57") (pin "2") (pinfunction "2_2") (pintype "passive"))
      (node (ref "U22") (pin "10") (pinfunction "3B_10") (pintype "input"))
      (node (ref "U22") (pin "9") (pinfunction "3A_9") (pintype "input"))
      (node (ref "U4") (pin "3") (pinfunction "I6_3") (pintype "input"))
    )
    (net (code "105") (name "/I7_A") (class "Default")
      (node (ref "R10") (pin "2") (pinfunction "2_2") (pintype "passive"))
      (node (ref "U1") (pin "2") (pinfunction "I7_2") (pintype "input"))
      (node (ref "U10") (pin "12") (pinfunction "4A_12") (pintype "input"))
      (node (ref "U10") (pin "13") (pinfunction "4B_13") (pintype "input"))
    )
    (net (code "106") (name "/I7_B") (class "Default")
      (node (ref "R26") (pin "2") (pinfunction "2_2") (pintype "passive"))
      (node (ref "U14") (pin "12") (pinfunction "4A_12") (pintype "input"))
      (node (ref "U14") (pin "13") (pinfunction "4B_13") (pintype "input"))
      (node (ref "U2") (pin "2") (pinfunction "I7_2") (pintype "input"))
    )
    (net (code "107") (name "/I7_C") (class "Default")
      (node (ref "R42") (pin "2") (pinfunction "2_2") (pintype "passive"))
      (node (ref "U18") (pin "12") (pinfunction "4A_12") (pintype "input"))
      (node (ref "U18") (pin "13") (pinfunction "4B_13") (pintype "input"))
      (node (ref "U3") (pin "2") (pinfunction "I7_2") (pintype "input"))
    )
    (net (code "108") (name "/I7_D") (class "Default")
      (node (ref "R58") (pin "2") (pinfunction "2_2") (pintype "passive"))
      (node (ref "U22") (pin "12") (pinfunction "4A_12") (pintype "input"))
      (node (ref "U22") (pin "13") (pinfunction "4B_13") (pintype "input"))
      (node (ref "U4") (pin "2") (pinfunction "I7_2") (pintype "input"))
    )
    (net (code "109") (name "/I8_A") (class "Default")
      (node (ref "R12") (pin "2") (pinfunction "2_2") (pintype "passive"))
      (node (ref "U1") (pin "23") (pinfunction "I8_23") (pintype "input"))
      (node (ref "U11") (pin "1") (pinfunction "1A_1") (pintype "input"))
      (node (ref "U11") (pin "2") (pinfunction "1B_2") (pintype "input"))
    )
    (net (code "110") (name "/I8_B") (class "Default")
      (node (ref "R27") (pin "2") (pinfunction "2_2") (pintype "passive"))
      (node (ref "U15") (pin "1") (pinfunction "1A_1") (pintype "input"))
      (node (ref "U15") (pin "2") (pinfunction "1B_2") (pintype "input"))
      (node (ref "U2") (pin "23") (pinfunction "I8_23") (pintype "input"))
    )
    (net (code "111") (name "/I8_C") (class "Default")
      (node (ref "R43") (pin "2") (pinfunction "2_2") (pintype "passive"))
      (node (ref "U19") (pin "1") (pinfunction "1A_1") (pintype "input"))
      (node (ref "U19") (pin "2") (pinfunction "1B_2") (pintype "input"))
      (node (ref "U3") (pin "23") (pinfunction "I8_23") (pintype "input"))
    )
    (net (code "112") (name "/I8_D") (class "Default")
      (node (ref "R59") (pin "2") (pinfunction "2_2") (pintype "passive"))
      (node (ref "U23") (pin "1") (pinfunction "1A_1") (pintype "input"))
      (node (ref "U23") (pin "2") (pinfunction "1B_2") (pintype "input"))
      (node (ref "U4") (pin "23") (pinfunction "I8_23") (pintype "input"))
    )
    (net (code "113") (name "/I9_A") (class "Default")
      (node (ref "R11") (pin "2") (pinfunction "2_2") (pintype "passive"))
      (node (ref "U1") (pin "22") (pinfunction "I9_22") (pintype "input"))
      (node (ref "U11") (pin "4") (pinfunction "2A_4") (pintype "input"))
      (node (ref "U11") (pin "5") (pinfunction "2B_5") (pintype "input"))
    )
    (net (code "114") (name "/I9_B") (class "Default")
      (node (ref "R28") (pin "2") (pinfunction "2_2") (pintype "passive"))
      (node (ref "U15") (pin "4") (pinfunction "2A_4") (pintype "input"))
      (node (ref "U15") (pin "5") (pinfunction "2B_5") (pintype "input"))
      (node (ref "U2") (pin "22") (pinfunction "I9_22") (pintype "input"))
    )
    (net (code "115") (name "/I9_C") (class "Default")
      (node (ref "R44") (pin "2") (pinfunction "2_2") (pintype "passive"))
      (node (ref "U19") (pin "4") (pinfunction "2A_4") (pintype "input"))
      (node (ref "U19") (pin "5") (pinfunction "2B_5") (pintype "input"))
      (node (ref "U3") (pin "22") (pinfunction "I9_22") (pintype "input"))
    )
    (net (code "116") (name "/I9_D") (class "Default")
      (node (ref "R60") (pin "2") (pinfunction "2_2") (pintype "passive"))
      (node (ref "U23") (pin "4") (pinfunction "2A_4") (pintype "input"))
      (node (ref "U23") (pin "5") (pinfunction "2B_5") (pintype "input"))
      (node (ref "U4") (pin "22") (pinfunction "I9_22") (pintype "input"))
    )
    (net (code "117") (name "/I10_A") (class "Default")
      (node (ref "R13") (pin "2") (pinfunction "2_2") (pintype "passive"))
      (node (ref "U1") (pin "21") (pinfunction "I10_21") (pintype "input"))
      (node (ref "U11") (pin "10") (pinfunction "3B_10") (pintype "input"))
      (node (ref "U11") (pin "9") (pinfunction "3A_9") (pintype "input"))
    )
    (net (code "118") (name "/I10_B") (class "Default")
      (node (ref "R29") (pin "2") (pinfunction "2_2") (pintype "passive"))
      (node (ref "U15") (pin "10") (pinfunction "3B_10") (pintype "input"))
      (node (ref "U15") (pin "9") (pinfunction "3A_9") (pintype "input"))
      (node (ref "U2") (pin "21") (pinfunction "I10_21") (pintype "input"))
    )
    (net (code "119") (name "/I10_C") (class "Default")
      (node (ref "R45") (pin "2") (pinfunction "2_2") (pintype "passive"))
      (node (ref "U19") (pin "10") (pinfunction "3B_10") (pintype "input"))
      (node (ref "U19") (pin "9") (pinfunction "3A_9") (pintype "input"))
      (node (ref "U3") (pin "21") (pinfunction "I10_21") (pintype "input"))
    )
    (net (code "120") (name "/I10_D") (class "Default")
      (node (ref "R61") (pin "2") (pinfunction "2_2") (pintype "passive"))
      (node (ref "U23") (pin "10") (pinfunction "3B_10") (pintype "input"))
      (node (ref "U23") (pin "9") (pinfunction "3A_9") (pintype "input"))
      (node (ref "U4") (pin "21") (pinfunction "I10_21") (pintype "input"))
    )
    (net (code "121") (name "/I11_A") (class "Default")
      (node (ref "R14") (pin "2") (pinfunction "2_2") (pintype "passive"))
      (node (ref "U1") (pin "20") (pinfunction "I11_20") (pintype "input"))
      (node (ref "U11") (pin "12") (pinfunction "4A_12") (pintype "input"))
      (node (ref "U11") (pin "13") (pinfunction "4B_13") (pintype "input"))
    )
    (net (code "122") (name "/I11_B") (class "Default")
      (node (ref "R30") (pin "2") (pinfunction "2_2") (pintype "passive"))
      (node (ref "U15") (pin "12") (pinfunction "4A_12") (pintype "input"))
      (node (ref "U15") (pin "13") (pinfunction "4B_13") (pintype "input"))
      (node (ref "U2") (pin "20") (pinfunction "I11_20") (pintype "input"))
    )
    (net (code "123") (name "/I11_C") (class "Default")
      (node (ref "R46") (pin "2") (pinfunction "2_2") (pintype "passive"))
      (node (ref "U19") (pin "12") (pinfunction "4A_12") (pintype "input"))
      (node (ref "U19") (pin "13") (pinfunction "4B_13") (pintype "input"))
      (node (ref "U3") (pin "20") (pinfunction "I11_20") (pintype "input"))
    )
    (net (code "124") (name "/I11_D") (class "Default")
      (node (ref "R62") (pin "2") (pinfunction "2_2") (pintype "passive"))
      (node (ref "U23") (pin "12") (pinfunction "4A_12") (pintype "input"))
      (node (ref "U23") (pin "13") (pinfunction "4B_13") (pintype "input"))
      (node (ref "U4") (pin "20") (pinfunction "I11_20") (pintype "input"))
    )
    (net (code "125") (name "/I12_A") (class "Default")
      (node (ref "R15") (pin "2") (pinfunction "2_2") (pintype "passive"))
      (node (ref "U1") (pin "19") (pinfunction "I12_19") (pintype "input"))
      (node (ref "U12") (pin "1") (pinfunction "1A_1") (pintype "input"))
      (node (ref "U12") (pin "2") (pinfunction "1B_2") (pintype "input"))
    )
    (net (code "126") (name "/I12_B") (class "Default")
      (node (ref "R31") (pin "2") (pinfunction "2_2") (pintype "passive"))
      (node (ref "U16") (pin "1") (pinfunction "1A_1") (pintype "input"))
      (node (ref "U16") (pin "2") (pinfunction "1B_2") (pintype "input"))
      (node (ref "U2") (pin "19") (pinfunction "I12_19") (pintype "input"))
    )
    (net (code "127") (name "/I12_C") (class "Default")
      (node (ref "R47") (pin "2") (pinfunction "2_2") (pintype "passive"))
      (node (ref "U20") (pin "1") (pinfunction "1A_1") (pintype "input"))
      (node (ref "U20") (pin "2") (pinfunction "1B_2") (pintype "input"))
      (node (ref "U3") (pin "19") (pinfunction "I12_19") (pintype "input"))
    )
    (net (code "128") (name "/I12_D") (class "Default")
      (node (ref "R63") (pin "2") (pinfunction "2_2") (pintype "passive"))
      (node (ref "U24") (pin "1") (pinfunction "1A_1") (pintype "input"))
      (node (ref "U24") (pin "2") (pinfunction "1B_2") (pintype "input"))
      (node (ref "U4") (pin "19") (pinfunction "I12_19") (pintype "input"))
    )
    (net (code "129") (name "/I13_A") (class "Default")
      (node (ref "R16") (pin "2") (pinfunction "2_2") (pintype "passive"))
      (node (ref "U1") (pin "18") (pinfunction "I13_18") (pintype "input"))
      (node (ref "U12") (pin "4") (pinfunction "2A_4") (pintype "input"))
      (node (ref "U12") (pin "5") (pinfunction "2B_5") (pintype "input"))
    )
    (net (code "130") (name "/I13_B") (class "Default")
      (node (ref "R32") (pin "2") (pinfunction "2_2") (pintype "passive"))
      (node (ref "U16") (pin "4") (pinfunction "2A_4") (pintype "input"))
      (node (ref "U16") (pin "5") (pinfunction "2B_5") (pintype "input"))
      (node (ref "U2") (pin "18") (pinfunction "I13_18") (pintype "input"))
    )
    (net (code "131") (name "/I13_C") (class "Default")
      (node (ref "R48") (pin "2") (pinfunction "2_2") (pintype "passive"))
      (node (ref "U20") (pin "4") (pinfunction "2A_4") (pintype "input"))
      (node (ref "U20") (pin "5") (pinfunction "2B_5") (pintype "input"))
      (node (ref "U3") (pin "18") (pinfunction "I13_18") (pintype "input"))
    )
    (net (code "132") (name "/I13_D") (class "Default")
      (node (ref "R64") (pin "2") (pinfunction "2_2") (pintype "passive"))
      (node (ref "U24") (pin "4") (pinfunction "2A_4") (pintype "input"))
      (node (ref "U24") (pin "5") (pinfunction "2B_5") (pintype "input"))
      (node (ref "U4") (pin "18") (pinfunction "I13_18") (pintype "input"))
    )
    (net (code "133") (name "/I14_A") (class "Default")
      (node (ref "R17") (pin "2") (pinfunction "2_2") (pintype "passive"))
      (node (ref "U1") (pin "17") (pinfunction "I14_17") (pintype "input"))
      (node (ref "U12") (pin "10") (pinfunction "3B_10") (pintype "input"))
      (node (ref "U12") (pin "9") (pinfunction "3A_9") (pintype "input"))
    )
    (net (code "134") (name "/I14_B") (class "Default")
      (node (ref "R33") (pin "2") (pinfunction "2_2") (pintype "passive"))
      (node (ref "U16") (pin "10") (pinfunction "3B_10") (pintype "input"))
      (node (ref "U16") (pin "9") (pinfunction "3A_9") (pintype "input"))
      (node (ref "U2") (pin "17") (pinfunction "I14_17") (pintype "input"))
    )
    (net (code "135") (name "/I14_C") (class "Default")
      (node (ref "R49") (pin "2") (pinfunction "2_2") (pintype "passive"))
      (node (ref "U20") (pin "10") (pinfunction "3B_10") (pintype "input"))
      (node (ref "U20") (pin "9") (pinfunction "3A_9") (pintype "input"))
      (node (ref "U3") (pin "17") (pinfunction "I14_17") (pintype "input"))
    )
    (net (code "136") (name "/I14_D") (class "Default")
      (node (ref "R65") (pin "2") (pinfunction "2_2") (pintype "passive"))
      (node (ref "U24") (pin "10") (pinfunction "3B_10") (pintype "input"))
      (node (ref "U24") (pin "9") (pinfunction "3A_9") (pintype "input"))
      (node (ref "U4") (pin "17") (pinfunction "I14_17") (pintype "input"))
    )
    (net (code "137") (name "/I15_A") (class "Default")
      (node (ref "R18") (pin "2") (pinfunction "2_2") (pintype "passive"))
      (node (ref "U1") (pin "16") (pinfunction "I15_16") (pintype "input"))
      (node (ref "U12") (pin "12") (pinfunction "4A_12") (pintype "input"))
      (node (ref "U12") (pin "13") (pinfunction "4B_13") (pintype "input"))
    )
    (net (code "138") (name "/I15_B") (class "Default")
      (node (ref "R34") (pin "2") (pinfunction "2_2") (pintype "passive"))
      (node (ref "U16") (pin "12") (pinfunction "4A_12") (pintype "input"))
      (node (ref "U16") (pin "13") (pinfunction "4B_13") (pintype "input"))
      (node (ref "U2") (pin "16") (pinfunction "I15_16") (pintype "input"))
    )
    (net (code "139") (name "/I15_C") (class "Default")
      (node (ref "R50") (pin "2") (pinfunction "2_2") (pintype "passive"))
      (node (ref "U20") (pin "12") (pinfunction "4A_12") (pintype "input"))
      (node (ref "U20") (pin "13") (pinfunction "4B_13") (pintype "input"))
      (node (ref "U3") (pin "16") (pinfunction "I15_16") (pintype "input"))
    )
    (net (code "140") (name "/I15_D") (class "Default")
      (node (ref "R66") (pin "2") (pinfunction "2_2") (pintype "passive"))
      (node (ref "U24") (pin "12") (pinfunction "4A_12") (pintype "input"))
      (node (ref "U24") (pin "13") (pinfunction "4B_13") (pintype "input"))
      (node (ref "U4") (pin "16") (pinfunction "I15_16") (pintype "input"))
    )
    (net (code "141") (name "/MCLK") (class "Default")
      (node (ref "CRYSTAL") (pin "4") (pinfunction "OUTPUT_4") (pintype "output"))
      (node (ref "U5") (pin "1") (pinfunction "CLKIN_1") (pintype "input"))
      (node (ref "U6") (pin "1") (pinfunction "CLKIN_1") (pintype "input"))
      (node (ref "U7") (pin "1") (pinfunction "CLKIN_1") (pintype "input"))
      (node (ref "U8") (pin "1") (pinfunction "CLKIN_1") (pintype "input"))
    )
    (net (code "142") (name "/MCLK0_A") (class "Default")
      (node (ref "J17") (pin "6") (pinfunction "6_6") (pintype "passive"))
      (node (ref "U5") (pin "3") (pinfunction "1Y0_3") (pintype "output"))
    )
    (net (code "143") (name "/MCLK0_B") (class "Default")
      (node (ref "J4") (pin "6") (pinfunction "6_6") (pintype "passive"))
      (node (ref "U6") (pin "3") (pinfunction "1Y0_3") (pintype "output"))
    )
    (net (code "144") (name "/MCLK0_C") (class "Default")
      (node (ref "J19") (pin "6") (pinfunction "6_6") (pintype "passive"))
      (node (ref "U7") (pin "3") (pinfunction "1Y0_3") (pintype "output"))
    )
    (net (code "145") (name "/MCLK0_D") (class "Default")
      (node (ref "J5") (pin "6") (pinfunction "6_6") (pintype "passive"))
      (node (ref "U8") (pin "3") (pinfunction "1Y0_3") (pintype "output"))
    )
    (net (code "146") (name "/MCLK1_A") (class "Default")
      (node (ref "J2") (pin "4") (pinfunction "4_4") (pintype "passive"))
      (node (ref "U5") (pin "5") (pinfunction "1Y1_5") (pintype "output"))
    )
    (net (code "147") (name "/MCLK1_B") (class "Default")
      (node (ref "J6") (pin "4") (pinfunction "4_4") (pintype "passive"))
      (node (ref "U6") (pin "5") (pinfunction "1Y1_5") (pintype "output"))
    )
    (net (code "148") (name "/MCLK1_C") (class "Default")
      (node (ref "J10") (pin "4") (pinfunction "4_4") (pintype "passive"))
      (node (ref "U7") (pin "5") (pinfunction "1Y1_5") (pintype "output"))
    )
    (net (code "149") (name "/MCLK1_D") (class "Default")
      (node (ref "J14") (pin "4") (pinfunction "4_4") (pintype "passive"))
      (node (ref "U8") (pin "5") (pinfunction "1Y1_5") (pintype "output"))
    )
    (net (code "150") (name "/MCLK2_A") (class "Default")
      (node (ref "J3") (pin "4") (pinfunction "4_4") (pintype "passive"))
      (node (ref "U5") (pin "7") (pinfunction "1Y2_7") (pintype "output"))
    )
    (net (code "151") (name "/MCLK2_B") (class "Default")
      (node (ref "J7") (pin "4") (pinfunction "4_4") (pintype "passive"))
      (node (ref "U6") (pin "7") (pinfunction "1Y2_7") (pintype "output"))
    )
    (net (code "152") (name "/MCLK2_C") (class "Default")
      (node (ref "J11") (pin "4") (pinfunction "4_4") (pintype "passive"))
      (node (ref "U7") (pin "7") (pinfunction "1Y2_7") (pintype "output"))
    )
    (net (code "153") (name "/MCLK2_D") (class "Default")
      (node (ref "J15") (pin "4") (pinfunction "4_4") (pintype "passive"))
      (node (ref "U8") (pin "7") (pinfunction "1Y2_7") (pintype "output"))
    )
    (net (code "154") (name "/MCLK3_A") (class "Default")
      (node (ref "J1") (pin "6") (pinfunction "6_6") (pintype "passive"))
      (node (ref "U5") (pin "8") (pinfunction "1Y3_8") (pintype "output"))
    )
    (net (code "155") (name "/MCLK3_B") (class "Default")
      (node (ref "J18") (pin "6") (pinfunction "6_6") (pintype "passive"))
      (node (ref "U6") (pin "8") (pinfunction "1Y3_8") (pintype "output"))
    )
    (net (code "156") (name "/MCLK3_C") (class "Default")
      (node (ref "J20") (pin "6") (pinfunction "6_6") (pintype "passive"))
      (node (ref "U7") (pin "8") (pinfunction "1Y3_8") (pintype "output"))
    )
    (net (code "157") (name "/MCLK3_D") (class "Default")
      (node (ref "J8") (pin "6") (pinfunction "6_6") (pintype "passive"))
      (node (ref "U8") (pin "8") (pinfunction "1Y3_8") (pintype "output"))
    )
    (net (code "158") (name "/MUX_EN") (class "Default")
      (node (ref "CN7") (pin "9") (pinfunction "9_9") (pintype "passive"))
      (node (ref "U1") (pin "15") (pinfunction "~{E}_15") (pintype "input"))
      (node (ref "U2") (pin "15") (pinfunction "~{E}_15") (pintype "input"))
    )
    (net (code "159") (name "/MUX_EN_B") (class "Default")
      (node (ref "CN9") (pin "1") (pinfunction "1_1") (pintype "passive"))
      (node (ref "MUX") (pin "6") (pinfunction "E~{}_6") (pintype "bidirectional"))
      (node (ref "U3") (pin "15") (pinfunction "~{E}_15") (pintype "input"))
      (node (ref "U4") (pin "15") (pinfunction "~{E}_15") (pintype "input"))
    )
    (net (code "160") (name "/PSELECT") (class "Default")
      (node (ref "CN10") (pin "7") (pinfunction "7_7") (pintype "passive"))
      (node (ref "J1") (pin "4") (pinfunction "4_4") (pintype "passive"))
      (node (ref "J10") (pin "2") (pinfunction "2_2") (pintype "passive"))
      (node (ref "J11") (pin "2") (pinfunction "2_2") (pintype "passive"))
      (node (ref "J14") (pin "2") (pinfunction "2_2") (pintype "passive"))
      (node (ref "J15") (pin "2") (pinfunction "2_2") (pintype "passive"))
      (node (ref "J17") (pin "4") (pinfunction "4_4") (pintype "passive"))
      (node (ref "J18") (pin "4") (pinfunction "4_4") (pintype "passive"))
      (node (ref "J19") (pin "4") (pinfunction "4_4") (pintype "passive"))
      (node (ref "J2") (pin "2") (pinfunction "2_2") (pintype "passive"))
      (node (ref "J20") (pin "4") (pinfunction "4_4") (pintype "passive"))
      (node (ref "J3") (pin "2") (pinfunction "2_2") (pintype "passive"))
      (node (ref "J4") (pin "4") (pinfunction "4_4") (pintype "passive"))
      (node (ref "J5") (pin "4") (pinfunction "4_4") (pintype "passive"))
      (node (ref "J6") (pin "2") (pinfunction "2_2") (pintype "passive"))
      (node (ref "J7") (pin "2") (pinfunction "2_2") (pintype "passive"))
      (node (ref "J8") (pin "4") (pinfunction "4_4") (pintype "passive"))
    )
    (net (code "161") (name "/RESET") (class "Default")
      (node (ref "CN8") (pin "4") (pinfunction "4_4") (pintype "passive"))
      (node (ref "J1") (pin "16") (pinfunction "16_16") (pintype "passive"))
      (node (ref "J10") (pin "14") (pinfunction "14_14") (pintype "passive"))
      (node (ref "J11") (pin "14") (pinfunction "14_14") (pintype "passive"))
      (node (ref "J14") (pin "14") (pinfunction "14_14") (pintype "passive"))
      (node (ref "J15") (pin "14") (pinfunction "14_14") (pintype "passive"))
      (node (ref "J17") (pin "16") (pinfunction "16_16") (pintype "passive"))
      (node (ref "J18") (pin "16") (pinfunction "16_16") (pintype "passive"))
      (node (ref "J19") (pin "16") (pinfunction "16_16") (pintype "passive"))
      (node (ref "J2") (pin "14") (pinfunction "14_14") (pintype "passive"))
      (node (ref "J20") (pin "16") (pinfunction "16_16") (pintype "passive"))
      (node (ref "J3") (pin "14") (pinfunction "14_14") (pintype "passive"))
      (node (ref "J4") (pin "16") (pinfunction "16_16") (pintype "passive"))
      (node (ref "J5") (pin "16") (pinfunction "16_16") (pintype "passive"))
      (node (ref "J6") (pin "14") (pinfunction "14_14") (pintype "passive"))
      (node (ref "J7") (pin "14") (pinfunction "14_14") (pintype "passive"))
      (node (ref "J8") (pin "16") (pinfunction "16_16") (pintype "passive"))
    )
    (net (code "162") (name "/S0_M4A") (class "Default")
      (node (ref "CN10") (pin "1") (pinfunction "1_1") (pintype "passive"))
      (node (ref "MUX") (pin "10") (pinfunction "S0_10") (pintype "bidirectional"))
    )
    (net (code "163") (name "/S0_M16") (class "Default")
      (node (ref "CN7") (pin "1") (pinfunction "1_1") (pintype "passive"))
      (node (ref "U1") (pin "10") (pinfunction "S0_10") (pintype "input"))
      (node (ref "U2") (pin "10") (pinfunction "S0_10") (pintype "input"))
    )
    (net (code "164") (name "/S0_M16_B") (class "Default")
      (node (ref "CN9") (pin "9") (pinfunction "9_9") (pintype "passive"))
      (node (ref "U3") (pin "10") (pinfunction "S0_10") (pintype "input"))
      (node (ref "U4") (pin "10") (pinfunction "S0_10") (pintype "input"))
    )
    (net (code "165") (name "/S1_M4A") (class "Default")
      (node (ref "CN10") (pin "3") (pinfunction "3_3") (pintype "passive"))
      (node (ref "MUX") (pin "9") (pinfunction "S1_9") (pintype "bidirectional"))
    )
    (net (code "166") (name "/S1_M16") (class "Default")
      (node (ref "CN7") (pin "3") (pinfunction "3_3") (pintype "passive"))
      (node (ref "U1") (pin "11") (pinfunction "S1_11") (pintype "input"))
      (node (ref "U2") (pin "11") (pinfunction "S1_11") (pintype "input"))
    )
    (net (code "167") (name "/S1_M16_B") (class "Default")
      (node (ref "CN9") (pin "10") (pinfunction "10_10") (pintype "passive"))
      (node (ref "U3") (pin "11") (pinfunction "S1_11") (pintype "input"))
      (node (ref "U4") (pin "11") (pinfunction "S1_11") (pintype "input"))
    )
    (net (code "168") (name "/S2_M16") (class "Default")
      (node (ref "CN7") (pin "5") (pinfunction "5_5") (pintype "passive"))
      (node (ref "U1") (pin "14") (pinfunction "S2_14") (pintype "input"))
      (node (ref "U2") (pin "14") (pinfunction "S2_14") (pintype "input"))
    )
    (net (code "169") (name "/S2_M16_B") (class "Default")
      (node (ref "CN9") (pin "7") (pinfunction "7_7") (pintype "passive"))
      (node (ref "U3") (pin "14") (pinfunction "S2_14") (pintype "input"))
      (node (ref "U4") (pin "14") (pinfunction "S2_14") (pintype "input"))
    )
    (net (code "170") (name "/S3_M16") (class "Default")
      (node (ref "CN7") (pin "7") (pinfunction "7_7") (pintype "passive"))
      (node (ref "U1") (pin "13") (pinfunction "S3_13") (pintype "input"))
      (node (ref "U2") (pin "13") (pinfunction "S3_13") (pintype "input"))
    )
    (net (code "171") (name "/S3_M16_B") (class "Default")
      (node (ref "CN9") (pin "5") (pinfunction "5_5") (pintype "passive"))
      (node (ref "U3") (pin "13") (pinfunction "S3_13") (pintype "input"))
      (node (ref "U4") (pin "13") (pinfunction "S3_13") (pintype "input"))
    )
    (net (code "172") (name "/SCLK_1") (class "Default")
      (node (ref "CN10") (pin "4") (pinfunction "4_4") (pintype "passive"))
      (node (ref "J10") (pin "11") (pinfunction "11_11") (pintype "passive"))
      (node (ref "J11") (pin "11") (pinfunction "11_11") (pintype "passive"))
      (node (ref "J18") (pin "13") (pinfunction "13_13") (pintype "passive"))
      (node (ref "J19") (pin "13") (pinfunction "13_13") (pintype "passive"))
      (node (ref "J20") (pin "13") (pinfunction "13_13") (pintype "passive"))
      (node (ref "J4") (pin "13") (pinfunction "13_13") (pintype "passive"))
      (node (ref "J6") (pin "11") (pinfunction "11_11") (pintype "passive"))
      (node (ref "J7") (pin "11") (pinfunction "11_11") (pintype "passive"))
    )
    (net (code "173") (name "/SCLK_2") (class "Default")
      (node (ref "CN7") (pin "4") (pinfunction "4_4") (pintype "passive"))
      (node (ref "J1") (pin "11") (pinfunction "11_11") (pintype "passive"))
      (node (ref "J17") (pin "11") (pinfunction "11_11") (pintype "passive"))
      (node (ref "J18") (pin "11") (pinfunction "11_11") (pintype "passive"))
      (node (ref "J2") (pin "9") (pinfunction "9_9") (pintype "passive"))
      (node (ref "J3") (pin "9") (pinfunction "9_9") (pintype "passive"))
      (node (ref "J4") (pin "11") (pinfunction "11_11") (pintype "passive"))
      (node (ref "J6") (pin "9") (pinfunction "9_9") (pintype "passive"))
      (node (ref "J7") (pin "9") (pinfunction "9_9") (pintype "passive"))
    )
    (net (code "174") (name "/SCLK_3") (class "Default")
      (node (ref "CN8") (pin "2") (pinfunction "2_2") (pintype "passive"))
      (node (ref "J1") (pin "13") (pinfunction "13_13") (pintype "passive"))
      (node (ref "J14") (pin "11") (pinfunction "11_11") (pintype "passive"))
      (node (ref "J15") (pin "11") (pinfunction "11_11") (pintype "passive"))
      (node (ref "J17") (pin "13") (pinfunction "13_13") (pintype "passive"))
      (node (ref "J2") (pin "11") (pinfunction "11_11") (pintype "passive"))
      (node (ref "J3") (pin "11") (pinfunction "11_11") (pintype "passive"))
      (node (ref "J5") (pin "13") (pinfunction "13_13") (pintype "passive"))
      (node (ref "J8") (pin "13") (pinfunction "13_13") (pintype "passive"))
    )
    (net (code "175") (name "/SCLK_5") (class "Default")
      (node (ref "CN9") (pin "6") (pinfunction "6_6") (pintype "passive"))
      (node (ref "J10") (pin "9") (pinfunction "9_9") (pintype "passive"))
      (node (ref "J11") (pin "9") (pinfunction "9_9") (pintype "passive"))
      (node (ref "J14") (pin "9") (pinfunction "9_9") (pintype "passive"))
      (node (ref "J15") (pin "9") (pinfunction "9_9") (pintype "passive"))
      (node (ref "J19") (pin "11") (pinfunction "11_11") (pintype "passive"))
      (node (ref "J20") (pin "11") (pinfunction "11_11") (pintype "passive"))
      (node (ref "J5") (pin "11") (pinfunction "11_11") (pintype "passive"))
      (node (ref "J8") (pin "11") (pinfunction "11_11") (pintype "passive"))
    )
    (net (code "176") (name "/SDATA_1") (class "Default")
      (node (ref "CN10") (pin "6") (pinfunction "6_6") (pintype "passive"))
      (node (ref "J10") (pin "12") (pinfunction "12_12") (pintype "passive"))
      (node (ref "J11") (pin "12") (pinfunction "12_12") (pintype "passive"))
      (node (ref "J18") (pin "14") (pinfunction "14_14") (pintype "passive"))
      (node (ref "J19") (pin "14") (pinfunction "14_14") (pintype "passive"))
      (node (ref "J20") (pin "14") (pinfunction "14_14") (pintype "passive"))
      (node (ref "J4") (pin "14") (pinfunction "14_14") (pintype "passive"))
      (node (ref "J6") (pin "12") (pinfunction "12_12") (pintype "passive"))
      (node (ref "J7") (pin "12") (pinfunction "12_12") (pintype "passive"))
    )
    (net (code "177") (name "/SDATA_3") (class "Default")
      (node (ref "CN8") (pin "6") (pinfunction "6_6") (pintype "passive"))
      (node (ref "J1") (pin "14") (pinfunction "14_14") (pintype "passive"))
      (node (ref "J14") (pin "12") (pinfunction "12_12") (pintype "passive"))
      (node (ref "J15") (pin "12") (pinfunction "12_12") (pintype "passive"))
      (node (ref "J17") (pin "14") (pinfunction "14_14") (pintype "passive"))
      (node (ref "J2") (pin "12") (pinfunction "12_12") (pintype "passive"))
      (node (ref "J3") (pin "12") (pinfunction "12_12") (pintype "passive"))
      (node (ref "J5") (pin "14") (pinfunction "14_14") (pintype "passive"))
      (node (ref "J8") (pin "14") (pinfunction "14_14") (pintype "passive"))
    )
    (net (code "178") (name "/SDO_2") (class "Default")
      (node (ref "CN7") (pin "6") (pinfunction "6_6") (pintype "passive"))
      (node (ref "J1") (pin "9") (pinfunction "9_9") (pintype "passive"))
      (node (ref "J17") (pin "9") (pinfunction "9_9") (pintype "passive"))
      (node (ref "J18") (pin "9") (pinfunction "9_9") (pintype "passive"))
      (node (ref "J2") (pin "7") (pinfunction "7_7") (pintype "passive"))
      (node (ref "J3") (pin "7") (pinfunction "7_7") (pintype "passive"))
      (node (ref "J4") (pin "9") (pinfunction "9_9") (pintype "passive"))
      (node (ref "J6") (pin "7") (pinfunction "7_7") (pintype "passive"))
      (node (ref "J7") (pin "7") (pinfunction "7_7") (pintype "passive"))
      (node (ref "R68") (pin "2") (pinfunction "2_2") (pintype "passive"))
    )
    (net (code "179") (name "/SDO_5") (class "Default")
      (node (ref "CN9") (pin "4") (pinfunction "4_4") (pintype "passive"))
      (node (ref "J10") (pin "7") (pinfunction "7_7") (pintype "passive"))
      (node (ref "J11") (pin "7") (pinfunction "7_7") (pintype "passive"))
      (node (ref "J14") (pin "7") (pinfunction "7_7") (pintype "passive"))
      (node (ref "J15") (pin "7") (pinfunction "7_7") (pintype "passive"))
      (node (ref "J19") (pin "9") (pinfunction "9_9") (pintype "passive"))
      (node (ref "J20") (pin "9") (pinfunction "9_9") (pintype "passive"))
      (node (ref "J5") (pin "9") (pinfunction "9_9") (pintype "passive"))
      (node (ref "J8") (pin "9") (pinfunction "9_9") (pintype "passive"))
      (node (ref "R67") (pin "1") (pinfunction "1_1") (pintype "passive"))
    )
    (net (code "180") (name "/SLEEP") (class "Default")
      (node (ref "CN8") (pin "8") (pinfunction "8_8") (pintype "passive"))
      (node (ref "J1") (pin "15") (pinfunction "15_15") (pintype "passive"))
      (node (ref "J10") (pin "13") (pinfunction "13_13") (pintype "passive"))
      (node (ref "J11") (pin "13") (pinfunction "13_13") (pintype "passive"))
      (node (ref "J14") (pin "13") (pinfunction "13_13") (pintype "passive"))
      (node (ref "J15") (pin "13") (pinfunction "13_13") (pintype "passive"))
      (node (ref "J17") (pin "15") (pinfunction "15_15") (pintype "passive"))
      (node (ref "J18") (pin "15") (pinfunction "15_15") (pintype "passive"))
      (node (ref "J19") (pin "15") (pinfunction "15_15") (pintype "passive"))
      (node (ref "J2") (pin "13") (pinfunction "13_13") (pintype "passive"))
      (node (ref "J20") (pin "15") (pinfunction "15_15") (pintype "passive"))
      (node (ref "J3") (pin "13") (pinfunction "13_13") (pintype "passive"))
      (node (ref "J4") (pin "15") (pinfunction "15_15") (pintype "passive"))
      (node (ref "J5") (pin "15") (pinfunction "15_15") (pintype "passive"))
      (node (ref "J6") (pin "13") (pinfunction "13_13") (pintype "passive"))
      (node (ref "J7") (pin "13") (pinfunction "13_13") (pintype "passive"))
      (node (ref "J8") (pin "15") (pinfunction "15_15") (pintype "passive"))
    )
    (net (code "181") (name "/VIN") (class "Default")
      (node (ref "C11") (pin "1") (pinfunction "1_1") (pintype "passive"))
      (node (ref "C12") (pin "1") (pinfunction "1_1") (pintype "passive"))
      (node (ref "JP1") (pin "1") (pinfunction "1_1") (pintype "passive"))
      (node (ref "SJ1") (pin "1") (pinfunction "1_1") (pintype "passive"))
      (node (ref "U$1") (pin "3") (pinfunction "VIN_3") (pintype "bidirectional"))
      (node (ref "U$1") (pin "5") (pinfunction "EN_5") (pintype "bidirectional"))
    )
    (net (code "182") (name "GND") (class "Default")
      (node (ref "C1") (pin "2") (pinfunction "2_2") (pintype "passive"))
      (node (ref "C10") (pin "2") (pinfunction "2_2") (pintype "passive"))
      (node (ref "C11") (pin "2") (pinfunction "2_2") (pintype "passive"))
      (node (ref "C12") (pin "2") (pinfunction "2_2") (pintype "passive"))
      (node (ref "C13") (pin "2") (pinfunction "2_2") (pintype "passive"))
      (node (ref "C14") (pin "2") (pinfunction "2_2") (pintype "passive"))
      (node (ref "C16") (pin "2") (pinfunction "2_2") (pintype "passive"))
      (node (ref "C17") (pin "2") (pinfunction "2_2") (pintype "passive"))
      (node (ref "C18") (pin "2") (pinfunction "2_2") (pintype "passive"))
      (node (ref "C19") (pin "2") (pinfunction "2_2") (pintype "passive"))
      (node (ref "C2") (pin "2") (pinfunction "2_2") (pintype "passive"))
      (node (ref "C20") (pin "2") (pinfunction "2_2") (pintype "passive"))
      (node (ref "C21") (pin "2") (pinfunction "2_2") (pintype "passive"))
      (node (ref "C22") (pin "2") (pinfunction "2_2") (pintype "passive"))
      (node (ref "C23") (pin "2") (pinfunction "2_2") (pintype "passive"))
      (node (ref "C24") (pin "2") (pinfunction "2_2") (pintype "passive"))
      (node (ref "C25") (pin "2") (pinfunction "2_2") (pintype "passive"))
      (node (ref "C26") (pin "2") (pinfunction "2_2") (pintype "passive"))
      (node (ref "C27") (pin "2") (pinfunction "2_2") (pintype "passive"))
      (node (ref "C28") (pin "2") (pinfunction "2_2") (pintype "passive"))
      (node (ref "C29") (pin "2") (pinfunction "2_2") (pintype "passive"))
      (node (ref "C3") (pin "2") (pinfunction "2_2") (pintype "passive"))
      (node (ref "C30") (pin "2") (pinfunction "2_2") (pintype "passive"))
      (node (ref "C31") (pin "2") (pinfunction "2_2") (pintype "passive"))
      (node (ref "C4") (pin "2") (pinfunction "2_2") (pintype "passive"))
      (node (ref "C5") (pin "2") (pinfunction "2_2") (pintype "passive"))
      (node (ref "C6") (pin "2") (pinfunction "2_2") (pintype "passive"))
      (node (ref "C7") (pin "2") (pinfunction "2_2") (pintype "passive"))
      (node (ref "C8") (pin "2") (pinfunction "2_2") (pintype "passive"))
      (node (ref "C9") (pin "1") (pinfunction "1_1") (pintype "passive"))
      (node (ref "CN10") (pin "5") (pinfunction "5_5") (pintype "passive"))
      (node (ref "CN7") (pin "2") (pinfunction "2_2") (pintype "passive"))
      (node (ref "CN8") (pin "7") (pinfunction "7_7") (pintype "passive"))
      (node (ref "CN9") (pin "3") (pinfunction "3_3") (pintype "passive"))
      (node (ref "CRYSTAL") (pin "3") (pinfunction "GND_3") (pintype "power_in"))
      (node (ref "J1") (pin "2") (pinfunction "2_2") (pintype "passive"))
      (node (ref "J17") (pin "2") (pinfunction "2_2") (pintype "passive"))
      (node (ref "J18") (pin "2") (pinfunction "2_2") (pintype "passive"))
      (node (ref "J19") (pin "2") (pinfunction "2_2") (pintype "passive"))
      (node (ref "J20") (pin "2") (pinfunction "2_2") (pintype "passive"))
      (node (ref "J4") (pin "2") (pinfunction "2_2") (pintype "passive"))
      (node (ref "J5") (pin "2") (pinfunction "2_2") (pintype "passive"))
      (node (ref "J8") (pin "2") (pinfunction "2_2") (pintype "passive"))
      (node (ref "JP1") (pin "2") (pinfunction "2_2") (pintype "passive"))
      (node (ref "JP1") (pin "3") (pinfunction "3_3") (pintype "passive"))
      (node (ref "MUX") (pin "7") (pinfunction "VEE_7") (pintype "bidirectional"))
      (node (ref "MUX") (pin "8") (pinfunction "GND_8") (pintype "bidirectional"))
      (node (ref "R10") (pin "1") (pinfunction "1_1") (pintype "passive"))
      (node (ref "R11") (pin "1") (pinfunction "1_1") (pintype "passive"))
      (node (ref "R12") (pin "1") (pinfunction "1_1") (pintype "passive"))
      (node (ref "R13") (pin "1") (pinfunction "1_1") (pintype "passive"))
      (node (ref "R14") (pin "1") (pinfunction "1_1") (pintype "passive"))
      (node (ref "R15") (pin "1") (pinfunction "1_1") (pintype "passive"))
      (node (ref "R16") (pin "1") (pinfunction "1_1") (pintype "passive"))
      (node (ref "R17") (pin "1") (pinfunction "1_1") (pintype "passive"))
      (node (ref "R18") (pin "1") (pinfunction "1_1") (pintype "passive"))
      (node (ref "R19") (pin "1") (pinfunction "1_1") (pintype "passive"))
      (node (ref "R2") (pin "1") (pinfunction "1_1") (pintype "passive"))
      (node (ref "R20") (pin "1") (pinfunction "1_1") (pintype "passive"))
      (node (ref "R21") (pin "1") (pinfunction "1_1") (pintype "passive"))
      (node (ref "R22") (pin "1") (pinfunction "1_1") (pintype "passive"))
      (node (ref "R23") (pin "1") (pinfunction "1_1") (pintype "passive"))
      (node (ref "R24") (pin "1") (pinfunction "1_1") (pintype "passive"))
      (node (ref "R25") (pin "1") (pinfunction "1_1") (pintype "passive"))
      (node (ref "R26") (pin "1") (pinfunction "1_1") (pintype "passive"))
      (node (ref "R27") (pin "1") (pinfunction "1_1") (pintype "passive"))
      (node (ref "R28") (pin "1") (pinfunction "1_1") (pintype "passive"))
      (node (ref "R29") (pin "1") (pinfunction "1_1") (pintype "passive"))
      (node (ref "R3") (pin "1") (pinfunction "1_1") (pintype "passive"))
      (node (ref "R30") (pin "1") (pinfunction "1_1") (pintype "passive"))
      (node (ref "R31") (pin "1") (pinfunction "1_1") (pintype "passive"))
      (node (ref "R32") (pin "1") (pinfunction "1_1") (pintype "passive"))
      (node (ref "R33") (pin "1") (pinfunction "1_1") (pintype "passive"))
      (node (ref "R34") (pin "1") (pinfunction "1_1") (pintype "passive"))
      (node (ref "R35") (pin "1") (pinfunction "1_1") (pintype "passive"))
      (node (ref "R36") (pin "1") (pinfunction "1_1") (pintype "passive"))
      (node (ref "R37") (pin "1") (pinfunction "1_1") (pintype "passive"))
      (node (ref "R38") (pin "1") (pinfunction "1_1") (pintype "passive"))
      (node (ref "R39") (pin "1") (pinfunction "1_1") (pintype "passive"))
      (node (ref "R4") (pin "1") (pinfunction "1_1") (pintype "passive"))
      (node (ref "R40") (pin "1") (pinfunction "1_1") (pintype "passive"))
      (node (ref "R41") (pin "1") (pinfunction "1_1") (pintype "passive"))
      (node (ref "R42") (pin "1") (pinfunction "1_1") (pintype "passive"))
      (node (ref "R43") (pin "1") (pinfunction "1_1") (pintype "passive"))
      (node (ref "R44") (pin "1") (pinfunction "1_1") (pintype "passive"))
      (node (ref "R45") (pin "1") (pinfunction "1_1") (pintype "passive"))
      (node (ref "R46") (pin "1") (pinfunction "1_1") (pintype "passive"))
      (node (ref "R47") (pin "1") (pinfunction "1_1") (pintype "passive"))
      (node (ref "R48") (pin "1") (pinfunction "1_1") (pintype "passive"))
      (node (ref "R49") (pin "1") (pinfunction "1_1") (pintype "passive"))
      (node (ref "R5") (pin "1") (pinfunction "1_1") (pintype "passive"))
      (node (ref "R50") (pin "1") (pinfunction "1_1") (pintype "passive"))
      (node (ref "R51") (pin "1") (pinfunction "1_1") (pintype "passive"))
      (node (ref "R52") (pin "1") (pinfunction "1_1") (pintype "passive"))
      (node (ref "R53") (pin "1") (pinfunction "1_1") (pintype "passive"))
      (node (ref "R54") (pin "1") (pinfunction "1_1") (pintype "passive"))
      (node (ref "R55") (pin "1") (pinfunction "1_1") (pintype "passive"))
      (node (ref "R56") (pin "1") (pinfunction "1_1") (pintype "passive"))
      (node (ref "R57") (pin "1") (pinfunction "1_1") (pintype "passive"))
      (node (ref "R58") (pin "1") (pinfunction "1_1") (pintype "passive"))
      (node (ref "R59") (pin "1") (pinfunction "1_1") (pintype "passive"))
      (node (ref "R6") (pin "1") (pinfunction "1_1") (pintype "passive"))
      (node (ref "R60") (pin "1") (pinfunction "1_1") (pintype "passive"))
      (node (ref "R61") (pin "1") (pinfunction "1_1") (pintype "passive"))
      (node (ref "R62") (pin "1") (pinfunction "1_1") (pintype "passive"))
      (node (ref "R63") (pin "1") (pinfunction "1_1") (pintype "passive"))
      (node (ref "R64") (pin "1") (pinfunction "1_1") (pintype "passive"))
      (node (ref "R65") (pin "1") (pinfunction "1_1") (pintype "passive"))
      (node (ref "R66") (pin "1") (pinfunction "1_1") (pintype "passive"))
      (node (ref "R67") (pin "2") (pinfunction "2_2") (pintype "passive"))
      (node (ref "R68") (pin "1") (pinfunction "1_1") (pintype "passive"))
      (node (ref "R7") (pin "1") (pinfunction "1_1") (pintype "passive"))
      (node (ref "R8") (pin "1") (pinfunction "1_1") (pintype "passive"))
      (node (ref "R9") (pin "1") (pinfunction "1_1") (pintype "passive"))
      (node (ref "U$1") (pin "1") (pinfunction "GND_1") (pintype "bidirectional"))
      (node (ref "U1") (pin "12") (pinfunction "GND_12") (pintype "passive"))
      (node (ref "U10") (pin "7") (pinfunction "GND_7") (pintype "power_in"))
      (node (ref "U11") (pin "7") (pinfunction "GND_7") (pintype "power_in"))
      (node (ref "U12") (pin "7") (pinfunction "GND_7") (pintype "power_in"))
      (node (ref "U13") (pin "7") (pinfunction "GND_7") (pintype "power_in"))
      (node (ref "U14") (pin "7") (pinfunction "GND_7") (pintype "power_in"))
      (node (ref "U15") (pin "7") (pinfunction "GND_7") (pintype "power_in"))
      (node (ref "U16") (pin "7") (pinfunction "GND_7") (pintype "power_in"))
      (node (ref "U17") (pin "7") (pinfunction "GND_7") (pintype "power_in"))
      (node (ref "U18") (pin "7") (pinfunction "GND_7") (pintype "power_in"))
      (node (ref "U19") (pin "7") (pinfunction "GND_7") (pintype "power_in"))
      (node (ref "U2") (pin "12") (pinfunction "GND_12") (pintype "passive"))
      (node (ref "U20") (pin "7") (pinfunction "GND_7") (pintype "power_in"))
      (node (ref "U21") (pin "7") (pinfunction "GND_7") (pintype "power_in"))
      (node (ref "U22") (pin "7") (pinfunction "GND_7") (pintype "power_in"))
      (node (ref "U23") (pin "7") (pinfunction "GND_7") (pintype "power_in"))
      (node (ref "U24") (pin "7") (pinfunction "GND_7") (pintype "power_in"))
      (node (ref "U3") (pin "12") (pinfunction "GND_12") (pintype "passive"))
      (node (ref "U4") (pin "12") (pinfunction "GND_12") (pintype "passive"))
      (node (ref "U5") (pin "4") (pinfunction "GND_4") (pintype "passive"))
      (node (ref "U6") (pin "4") (pinfunction "GND_4") (pintype "passive"))
      (node (ref "U7") (pin "4") (pinfunction "GND_4") (pintype "passive"))
      (node (ref "U8") (pin "4") (pinfunction "GND_4") (pintype "passive"))
      (node (ref "U9") (pin "7") (pinfunction "GND_7") (pintype "power_in"))
    )
    (net (code "183") (name "Net-(U$1-SW)") (class "Default")
      (node (ref "C15") (pin "2") (pinfunction "2_2") (pintype "passive"))
      (node (ref "L1") (pin "1") (pinfunction "1_1") (pintype "passive"))
      (node (ref "U$1") (pin "2") (pinfunction "SW_2") (pintype "bidirectional"))
    )
    (net (code "184") (name "Net-(U$1-VBST)") (class "Default")
      (node (ref "C15") (pin "1") (pinfunction "1_1") (pintype "passive"))
      (node (ref "U$1") (pin "6") (pinfunction "VBST_6") (pintype "bidirectional"))
    )
    (net (code "185") (name "Net-(U$1-VFB)") (class "Default")
      (node (ref "R1") (pin "1") (pinfunction "1_1") (pintype "passive"))
      (node (ref "R2") (pin "2") (pinfunction "2_2") (pintype "passive"))
      (node (ref "U$1") (pin "4") (pinfunction "VFB_4") (pintype "bidirectional"))
    )
    (net (code "186") (name "unconnected-(CN7-Pad10)") (class "Default")
      (node (ref "CN7") (pin "10") (pinfunction "10_10") (pintype "passive"))
    )
    (net (code "187") (name "unconnected-(CN8-Pad1)") (class "Default")
      (node (ref "CN8") (pin "1") (pinfunction "1_1") (pintype "passive"))
    )
    (net (code "188") (name "unconnected-(CN8-Pad3)") (class "Default")
      (node (ref "CN8") (pin "3") (pinfunction "3_3") (pintype "passive"))
    )
    (net (code "189") (name "unconnected-(CN8-Pad5)") (class "Default")
      (node (ref "CN8") (pin "5") (pinfunction "5_5") (pintype "passive"))
    )
    (net (code "190") (name "unconnected-(CN9-Pad2)") (class "Default")
      (node (ref "CN9") (pin "2") (pinfunction "2_2") (pintype "passive"))
    )
    (net (code "191") (name "unconnected-(CN10-Pad2)") (class "Default")
      (node (ref "CN10") (pin "2") (pinfunction "2_2") (pintype "passive"))
    )
  )
)
